# samd_board_des.net
KiCad netlist of a schematic drawn in EAGLE
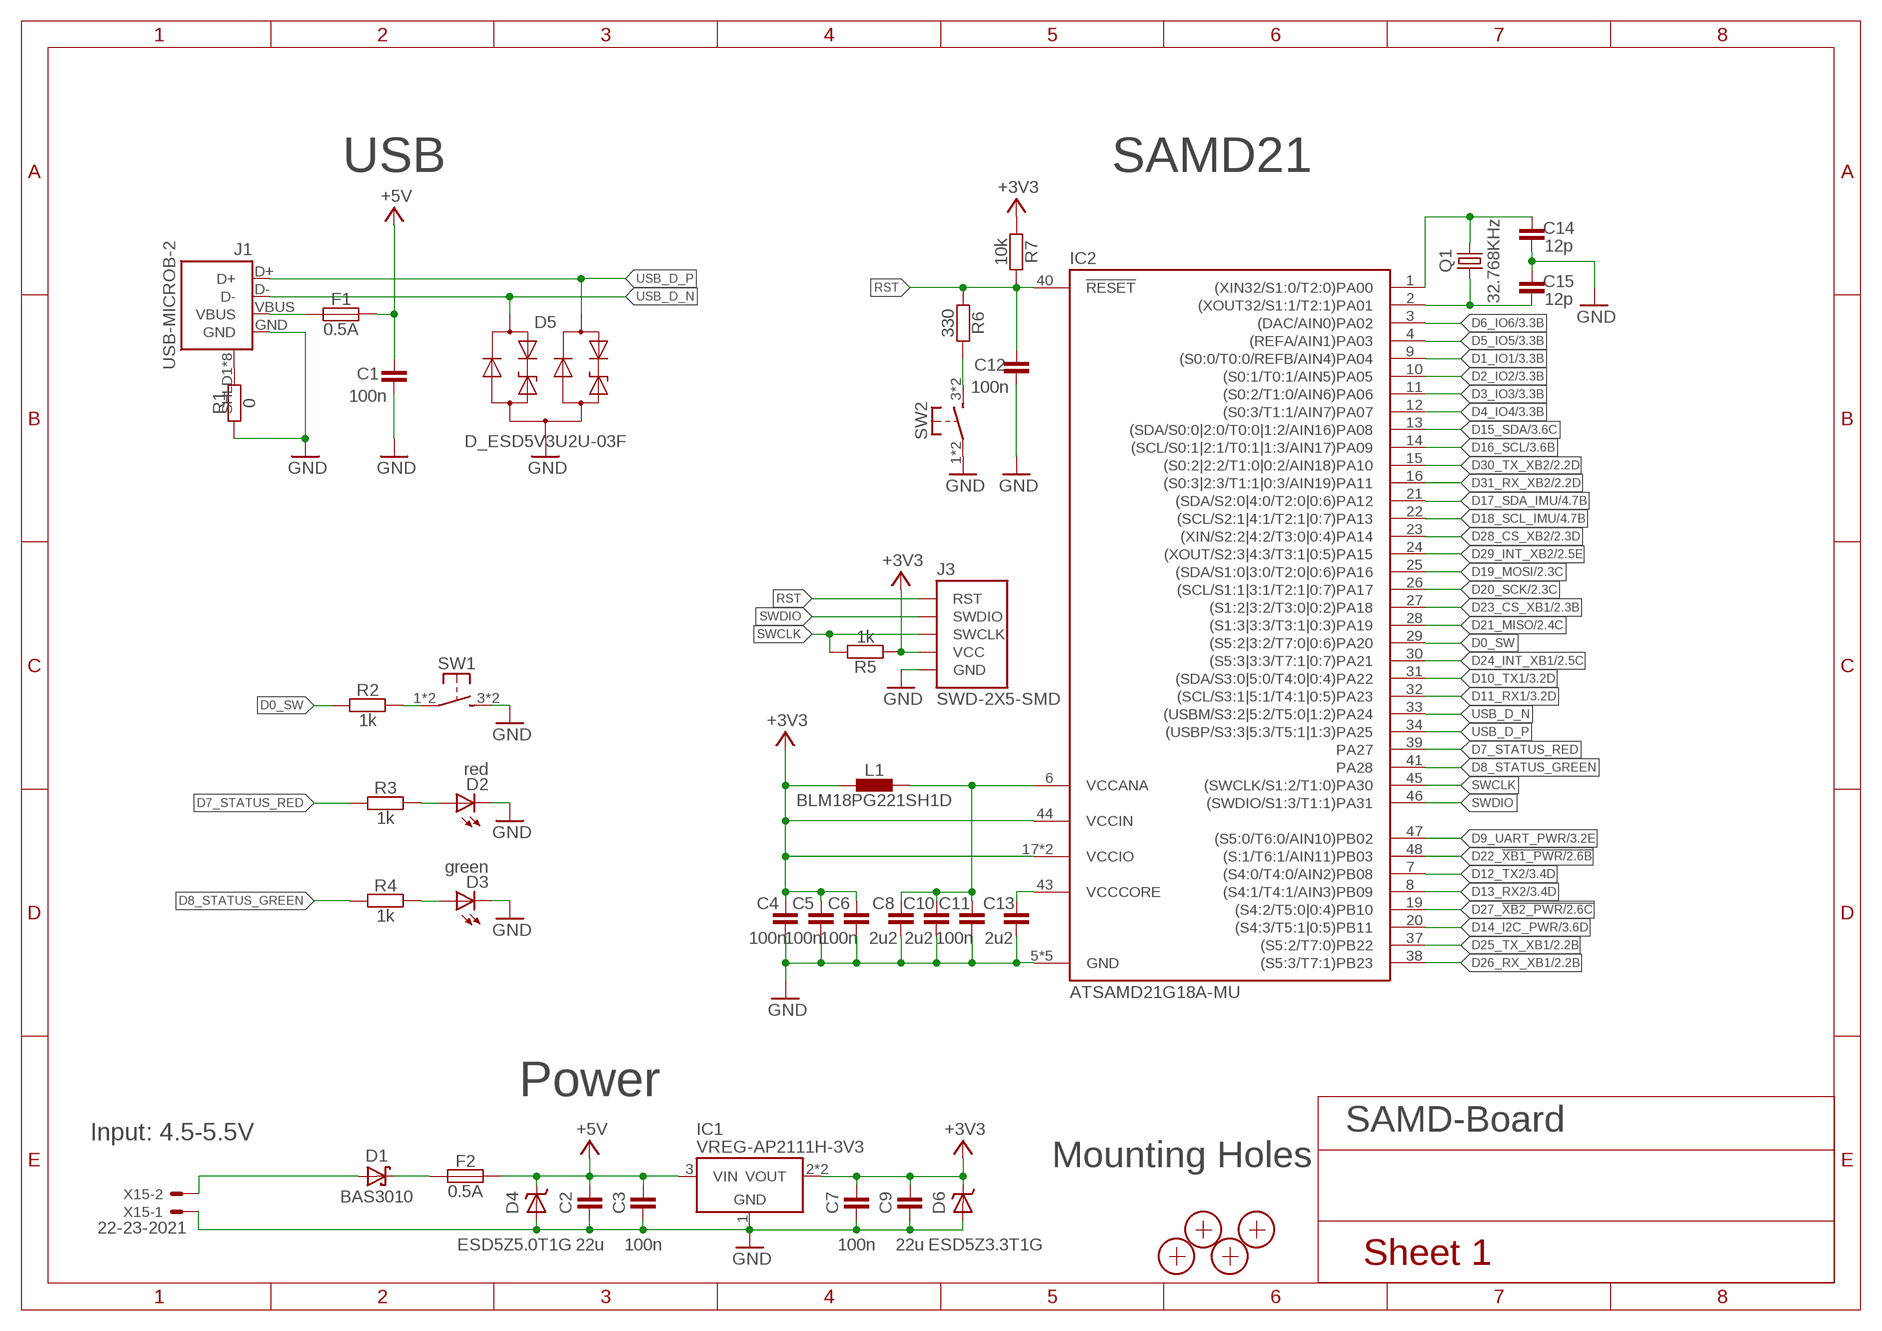
[diagram p0: schematic, sheet 1]
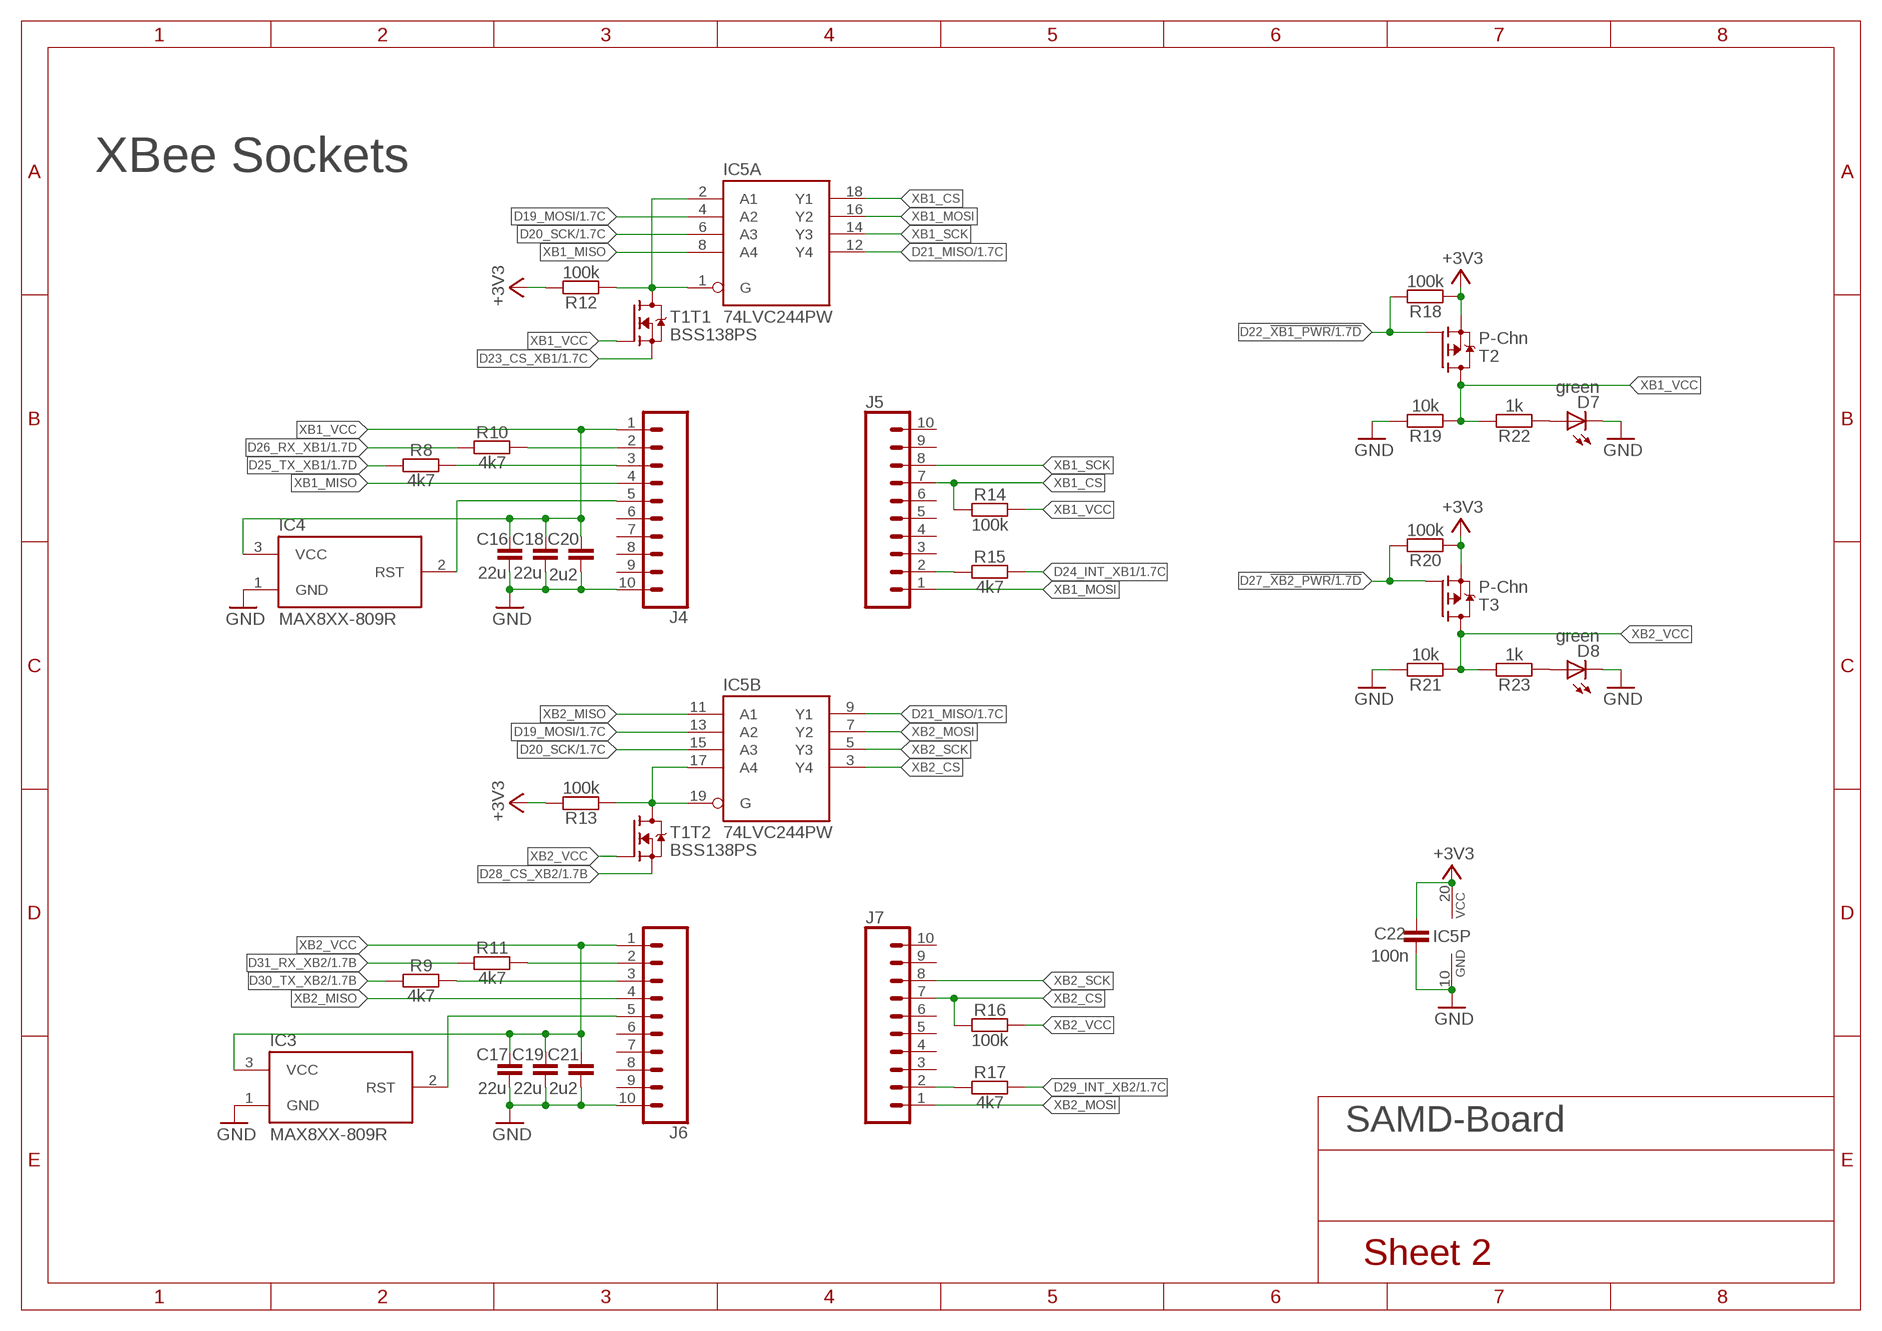
[diagram p1: schematic, sheet 2]
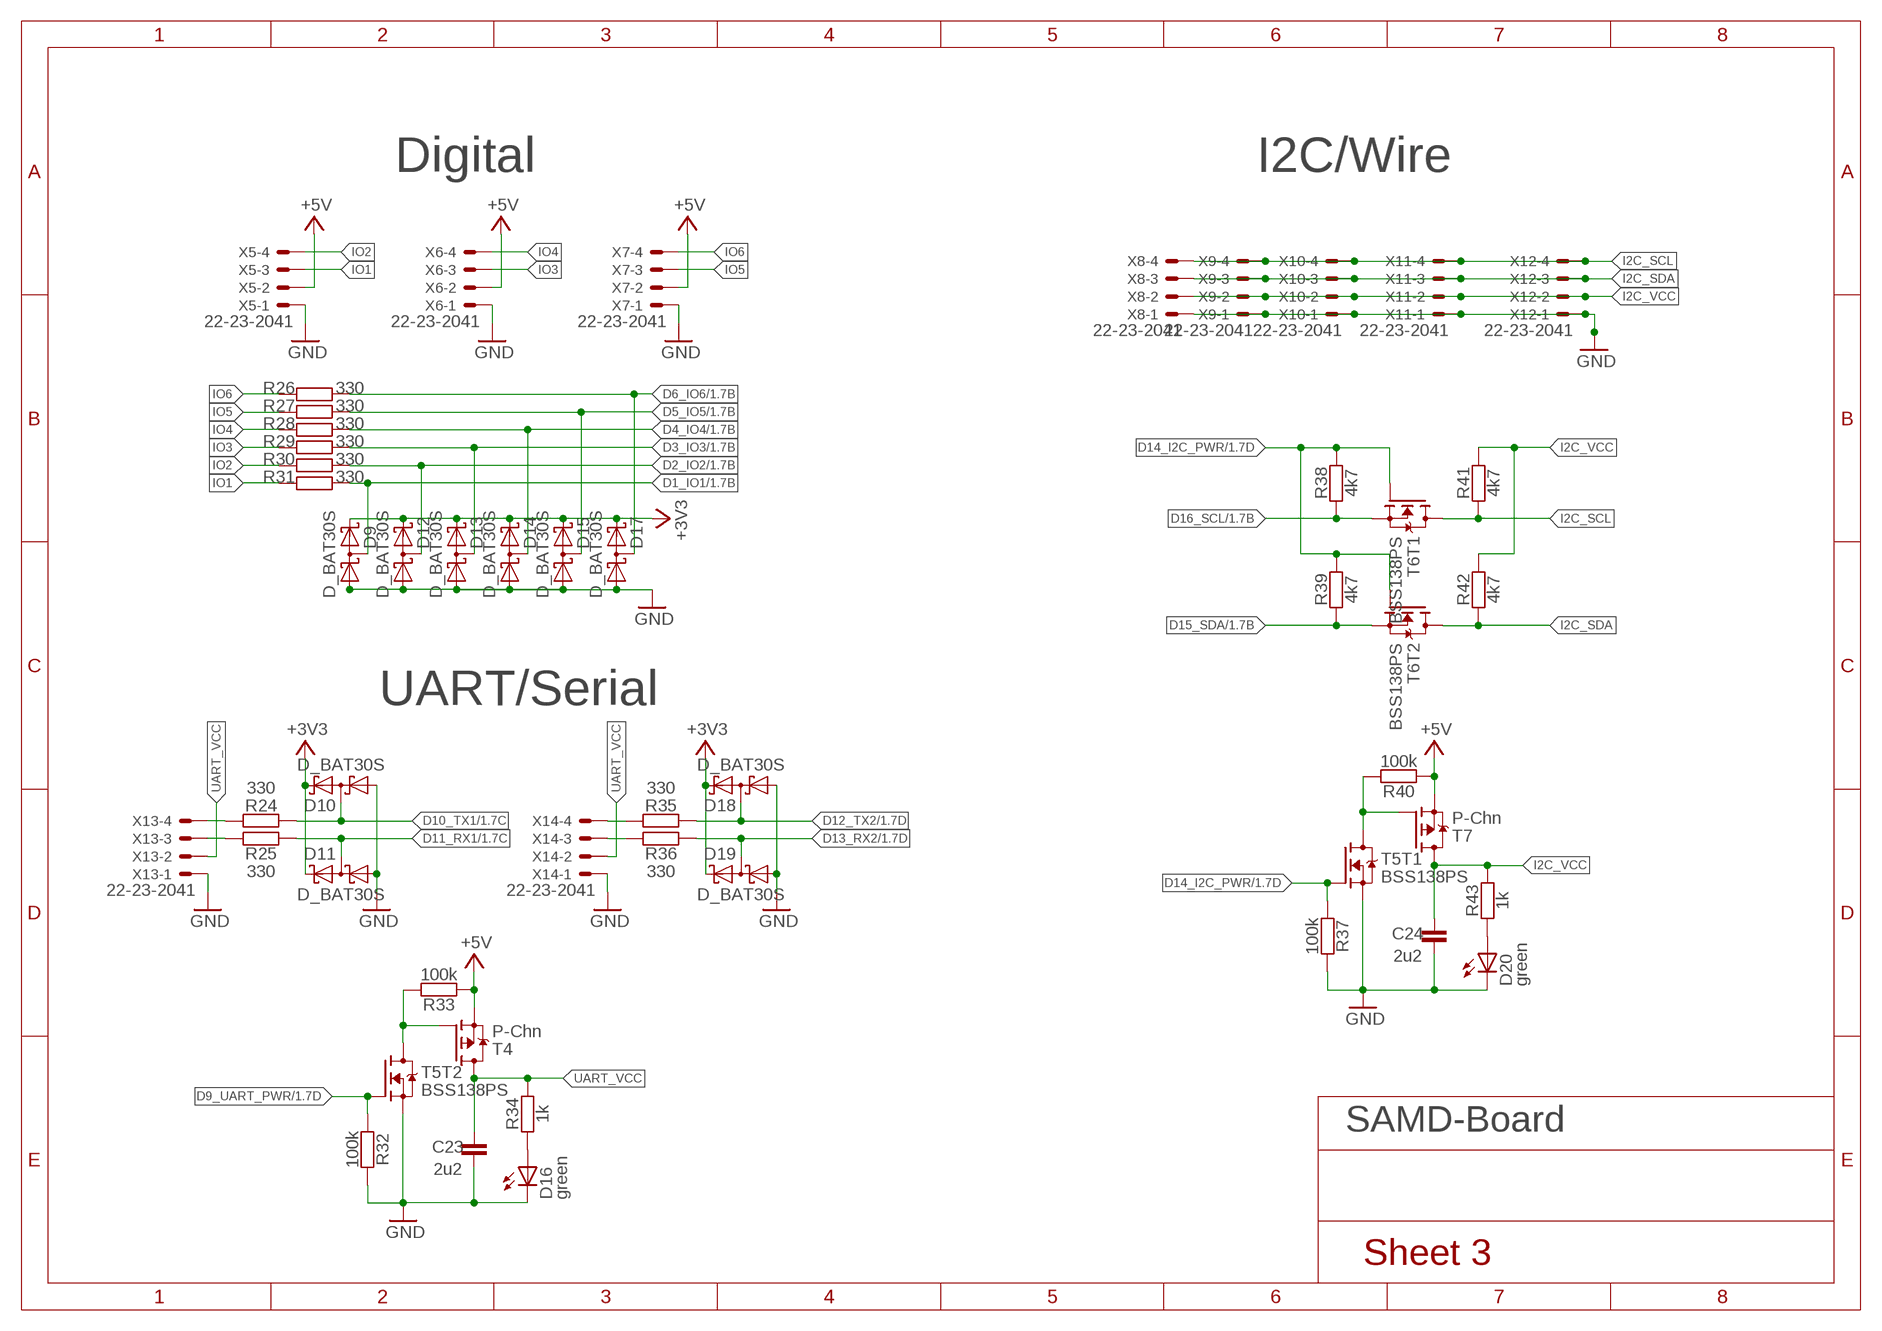
[diagram p2: schematic, sheet 3]
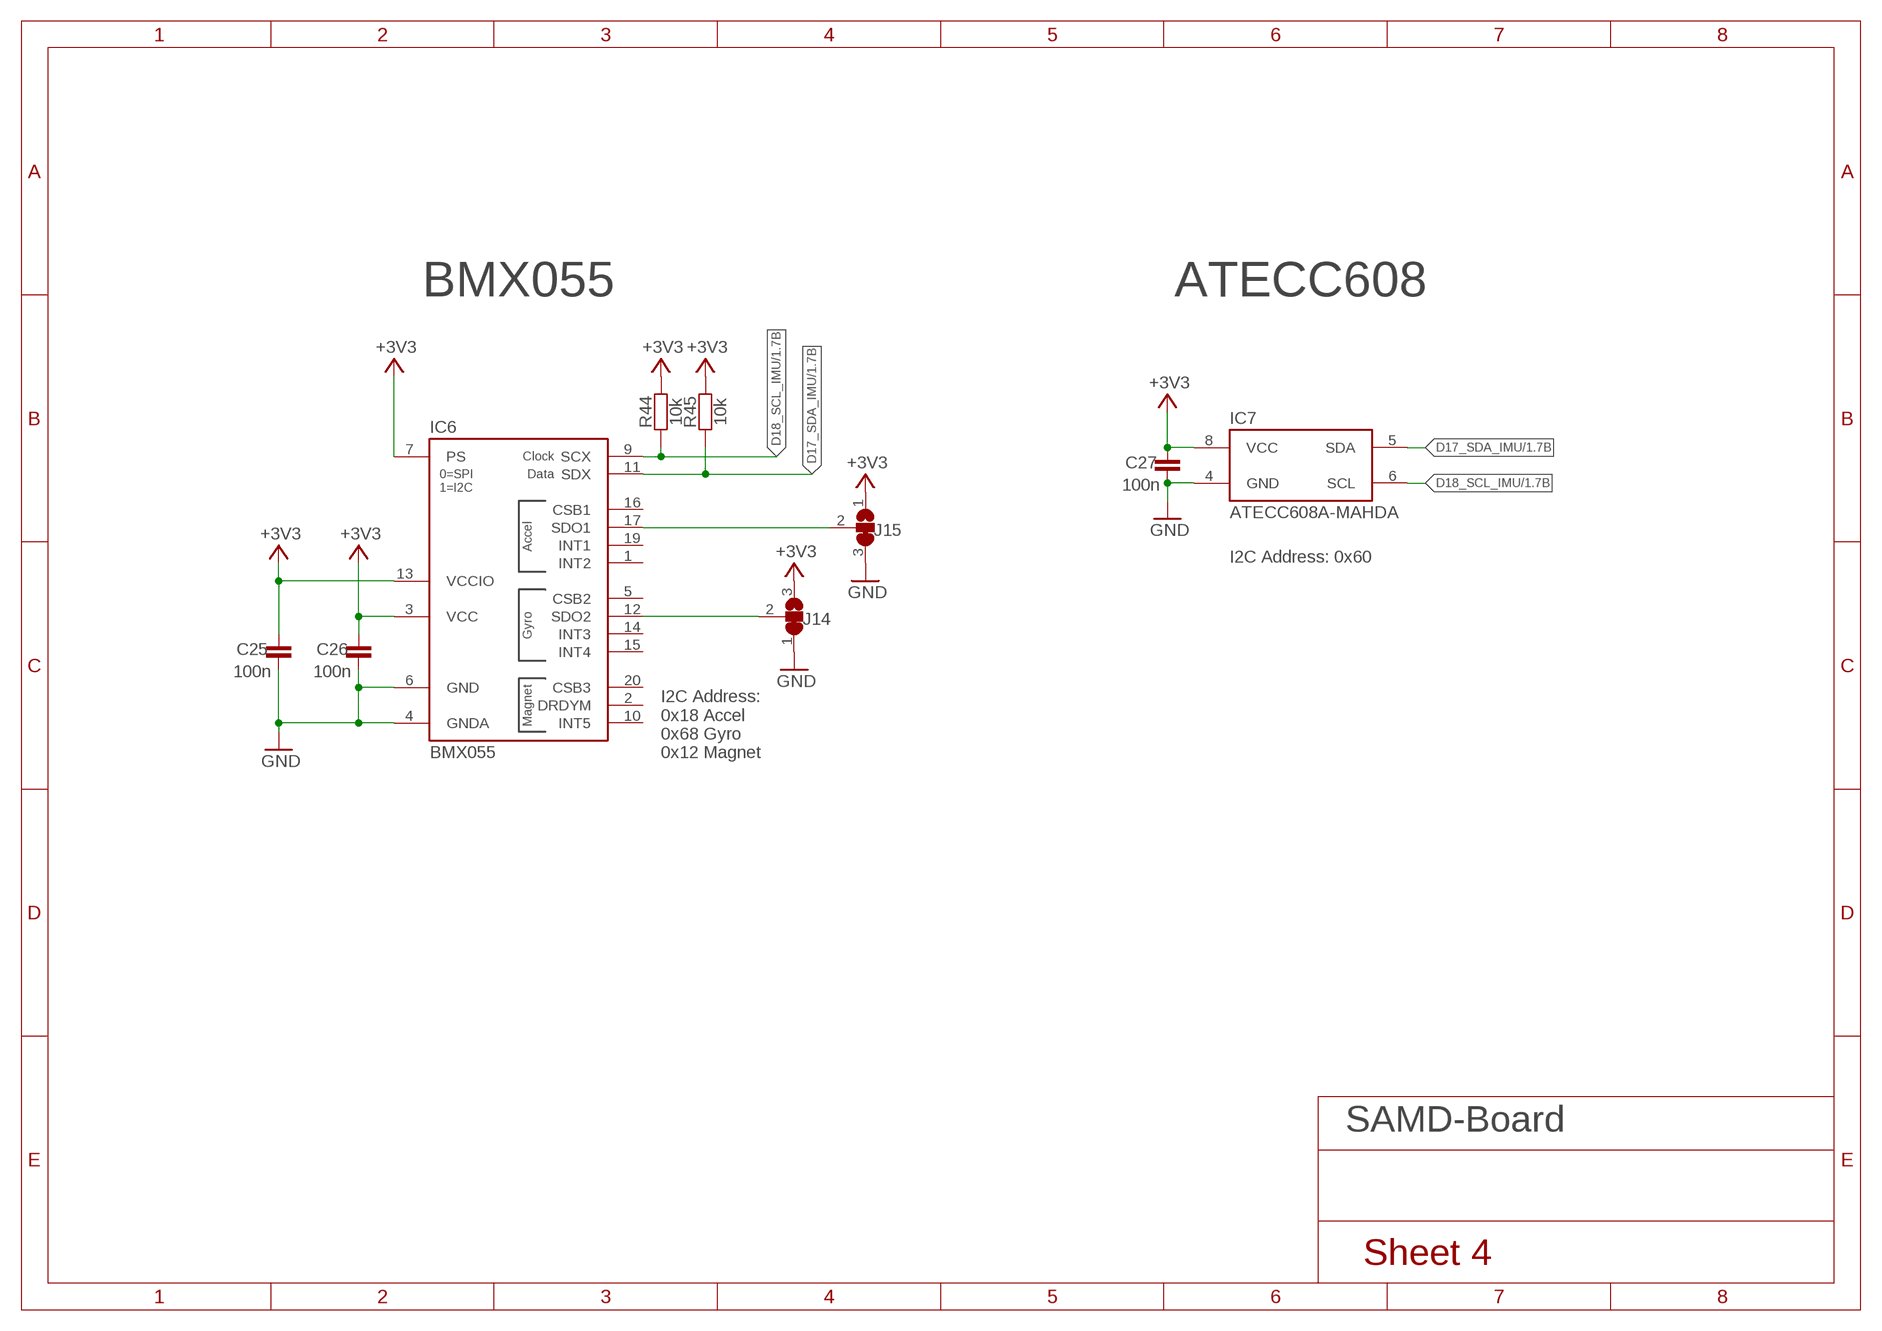
[diagram p3: schematic, sheet 4]

(export (version "E")
  (design (tool "Eeschema 10.0.6"))
  (components
    (comp (ref "C23")
      (value "2u2")
      (footprint "eagle-import:C0402")
      (libsource (lib "eagle-import") (part "CAPACITOR-0402"))
    )
    (comp (ref "C24")
      (value "2u2")
      (footprint "eagle-import:C0402")
      (libsource (lib "eagle-import") (part "CAPACITOR-0402"))
    )
    (comp (ref "D9")
      (value "D_BAT30S")
      (footprint "eagle-import:SOT323")
      (libsource (lib "eagle-import") (part "D_BAT30S"))
    )
    (comp (ref "D10")
      (value "D_BAT30S")
      (footprint "eagle-import:SOT323")
      (libsource (lib "eagle-import") (part "D_BAT30S"))
    )
    (comp (ref "D11")
      (value "D_BAT30S")
      (footprint "eagle-import:SOT323")
      (libsource (lib "eagle-import") (part "D_BAT30S"))
    )
    (comp (ref "D12")
      (value "D_BAT30S")
      (footprint "eagle-import:SOT323")
      (libsource (lib "eagle-import") (part "D_BAT30S"))
    )
    (comp (ref "D13")
      (value "D_BAT30S")
      (footprint "eagle-import:SOT323")
      (libsource (lib "eagle-import") (part "D_BAT30S"))
    )
    (comp (ref "D14")
      (value "D_BAT30S")
      (footprint "eagle-import:SOT323")
      (libsource (lib "eagle-import") (part "D_BAT30S"))
    )
    (comp (ref "D15")
      (value "D_BAT30S")
      (footprint "eagle-import:SOT323")
      (libsource (lib "eagle-import") (part "D_BAT30S"))
    )
    (comp (ref "D16")
      (value "green")
      (footprint "eagle-import:C0603")
      (libsource (lib "eagle-import") (part "LED-0603"))
    )
    (comp (ref "D17")
      (value "D_BAT30S")
      (footprint "eagle-import:SOT323")
      (libsource (lib "eagle-import") (part "D_BAT30S"))
    )
    (comp (ref "D18")
      (value "D_BAT30S")
      (footprint "eagle-import:SOT323")
      (libsource (lib "eagle-import") (part "D_BAT30S"))
    )
    (comp (ref "D19")
      (value "D_BAT30S")
      (footprint "eagle-import:SOT323")
      (libsource (lib "eagle-import") (part "D_BAT30S"))
    )
    (comp (ref "D20")
      (value "green")
      (footprint "eagle-import:C0603")
      (libsource (lib "eagle-import") (part "LED-0603"))
    )
    (comp (ref "R24")
      (value "330")
      (footprint "eagle-import:C0402")
      (libsource (lib "eagle-import") (part "RESISTOR-0402"))
    )
    (comp (ref "R25")
      (value "330")
      (footprint "eagle-import:C0402")
      (libsource (lib "eagle-import") (part "RESISTOR-0402"))
    )
    (comp (ref "R26")
      (value "330")
      (footprint "eagle-import:C0402")
      (libsource (lib "eagle-import") (part "RESISTOR-0402"))
    )
    (comp (ref "R27")
      (value "330")
      (footprint "eagle-import:C0402")
      (libsource (lib "eagle-import") (part "RESISTOR-0402"))
    )
    (comp (ref "R28")
      (value "330")
      (footprint "eagle-import:C0402")
      (libsource (lib "eagle-import") (part "RESISTOR-0402"))
    )
    (comp (ref "R29")
      (value "330")
      (footprint "eagle-import:C0402")
      (libsource (lib "eagle-import") (part "RESISTOR-0402"))
    )
    (comp (ref "R30")
      (value "330")
      (footprint "eagle-import:C0402")
      (libsource (lib "eagle-import") (part "RESISTOR-0402"))
    )
    (comp (ref "R31")
      (value "330")
      (footprint "eagle-import:C0402")
      (libsource (lib "eagle-import") (part "RESISTOR-0402"))
    )
    (comp (ref "R32")
      (value "100k")
      (footprint "eagle-import:C0402")
      (libsource (lib "eagle-import") (part "RESISTOR-0402"))
    )
    (comp (ref "R33")
      (value "100k")
      (footprint "eagle-import:C0402")
      (libsource (lib "eagle-import") (part "RESISTOR-0402"))
    )
    (comp (ref "R34")
      (value "1k")
      (footprint "eagle-import:C0402")
      (libsource (lib "eagle-import") (part "RESISTOR-0402"))
    )
    (comp (ref "R35")
      (value "330")
      (footprint "eagle-import:C0402")
      (libsource (lib "eagle-import") (part "RESISTOR-0402"))
    )
    (comp (ref "R36")
      (value "330")
      (footprint "eagle-import:C0402")
      (libsource (lib "eagle-import") (part "RESISTOR-0402"))
    )
    (comp (ref "R37")
      (value "100k")
      (footprint "eagle-import:C0402")
      (libsource (lib "eagle-import") (part "RESISTOR-0402"))
    )
    (comp (ref "R38")
      (value "4k7")
      (footprint "eagle-import:C0402")
      (libsource (lib "eagle-import") (part "RESISTOR-0402"))
    )
    (comp (ref "R39")
      (value "4k7")
      (footprint "eagle-import:C0402")
      (libsource (lib "eagle-import") (part "RESISTOR-0402"))
    )
    (comp (ref "R40")
      (value "100k")
      (footprint "eagle-import:C0402")
      (libsource (lib "eagle-import") (part "RESISTOR-0402"))
    )
    (comp (ref "R41")
      (value "4k7")
      (footprint "eagle-import:C0402")
      (libsource (lib "eagle-import") (part "RESISTOR-0402"))
    )
    (comp (ref "R42")
      (value "4k7")
      (footprint "eagle-import:C0402")
      (libsource (lib "eagle-import") (part "RESISTOR-0402"))
    )
    (comp (ref "R43")
      (value "1k")
      (footprint "eagle-import:C0402")
      (libsource (lib "eagle-import") (part "RESISTOR-0402"))
    )
    (comp (ref "T4")
      (value "P-Chn")
      (footprint "eagle-import:SOT23")
      (libsource (lib "eagle-import") (part "MOSFET-P-SOT23"))
    )
    (comp (ref "T5")
      (value "BSS138PS")
      (footprint "eagle-import:SOT363")
      (libsource (lib "eagle-import") (part "BSS138PS"))
    )
    (comp (ref "T6")
      (value "BSS138PS")
      (footprint "eagle-import:SOT363")
      (libsource (lib "eagle-import") (part "BSS138PS"))
    )
    (comp (ref "T7")
      (value "P-Chn")
      (footprint "eagle-import:SOT23")
      (libsource (lib "eagle-import") (part "MOSFET-P-SOT23"))
    )
    (comp (ref "X5")
      (value "22-23-2041")
      (footprint "eagle-import:22-23-2041")
      (fields (field (name "MF") "MOLEX"))
      (libsource (lib "eagle-import") (part "22-23-2041"))
    )
    (comp (ref "X6")
      (value "22-23-2041")
      (footprint "eagle-import:22-23-2041")
      (fields (field (name "MF") "MOLEX"))
      (libsource (lib "eagle-import") (part "22-23-2041"))
    )
    (comp (ref "X7")
      (value "22-23-2041")
      (footprint "eagle-import:22-23-2041")
      (fields (field (name "MF") "MOLEX"))
      (libsource (lib "eagle-import") (part "22-23-2041"))
    )
    (comp (ref "X8")
      (value "22-23-2041")
      (footprint "eagle-import:22-23-2041")
      (fields (field (name "MF") "MOLEX"))
      (libsource (lib "eagle-import") (part "22-23-2041"))
    )
    (comp (ref "X9")
      (value "22-23-2041")
      (footprint "eagle-import:22-23-2041")
      (fields (field (name "MF") "MOLEX"))
      (libsource (lib "eagle-import") (part "22-23-2041"))
    )
    (comp (ref "X10")
      (value "22-23-2041")
      (footprint "eagle-import:22-23-2041")
      (fields (field (name "MF") "MOLEX"))
      (libsource (lib "eagle-import") (part "22-23-2041"))
    )
    (comp (ref "X11")
      (value "22-23-2041")
      (footprint "eagle-import:22-23-2041")
      (fields (field (name "MF") "MOLEX"))
      (libsource (lib "eagle-import") (part "22-23-2041"))
    )
    (comp (ref "X12")
      (value "22-23-2041")
      (footprint "eagle-import:22-23-2041")
      (fields (field (name "MF") "MOLEX"))
      (libsource (lib "eagle-import") (part "22-23-2041"))
    )
    (comp (ref "X13")
      (value "22-23-2041")
      (footprint "eagle-import:22-23-2041")
      (fields (field (name "MF") "MOLEX"))
      (libsource (lib "eagle-import") (part "22-23-2041"))
    )
    (comp (ref "X14")
      (value "22-23-2041")
      (footprint "eagle-import:22-23-2041")
      (fields (field (name "MF") "MOLEX"))
      (libsource (lib "eagle-import") (part "22-23-2041"))
    )
    (comp (ref "C1")
      (value "100n")
      (footprint "eagle-import:C0402")
      (libsource (lib "eagle-import") (part "CAPACITOR-0402"))
    )
    (comp (ref "C2")
      (value "22u")
      (footprint "eagle-import:C0805")
      (libsource (lib "eagle-import") (part "CAPACITOR-0805"))
    )
    (comp (ref "C3")
      (value "100n")
      (footprint "eagle-import:C0402")
      (libsource (lib "eagle-import") (part "CAPACITOR-0402"))
    )
    (comp (ref "C4")
      (value "100n")
      (footprint "eagle-import:C0402")
      (libsource (lib "eagle-import") (part "CAPACITOR-0402"))
    )
    (comp (ref "C5")
      (value "100n")
      (footprint "eagle-import:C0402")
      (libsource (lib "eagle-import") (part "CAPACITOR-0402"))
    )
    (comp (ref "C6")
      (value "100n")
      (footprint "eagle-import:C0402")
      (libsource (lib "eagle-import") (part "CAPACITOR-0402"))
    )
    (comp (ref "C7")
      (value "100n")
      (footprint "eagle-import:C0402")
      (libsource (lib "eagle-import") (part "CAPACITOR-0402"))
    )
    (comp (ref "C8")
      (value "2u2")
      (footprint "eagle-import:C0402")
      (libsource (lib "eagle-import") (part "CAPACITOR-0402"))
    )
    (comp (ref "C9")
      (value "22u")
      (footprint "eagle-import:C0805")
      (libsource (lib "eagle-import") (part "CAPACITOR-0805"))
    )
    (comp (ref "C10")
      (value "2u2")
      (footprint "eagle-import:C0402")
      (libsource (lib "eagle-import") (part "CAPACITOR-0402"))
    )
    (comp (ref "C11")
      (value "100n")
      (footprint "eagle-import:C0402")
      (libsource (lib "eagle-import") (part "CAPACITOR-0402"))
    )
    (comp (ref "C12")
      (value "100n")
      (footprint "eagle-import:C0402")
      (libsource (lib "eagle-import") (part "CAPACITOR-0402"))
    )
    (comp (ref "C13")
      (value "2u2")
      (footprint "eagle-import:C0402")
      (libsource (lib "eagle-import") (part "CAPACITOR-0402"))
    )
    (comp (ref "C14")
      (value "12p")
      (footprint "eagle-import:C0402")
      (libsource (lib "eagle-import") (part "CAPACITOR-0402"))
    )
    (comp (ref "C15")
      (value "12p")
      (footprint "eagle-import:C0402")
      (libsource (lib "eagle-import") (part "CAPACITOR-0402"))
    )
    (comp (ref "D1")
      (value "BAS3010")
      (footprint "eagle-import:SOD323")
      (libsource (lib "eagle-import") (part "D_SCHOTTKY-SOD323"))
    )
    (comp (ref "D2")
      (value "red")
      (footprint "eagle-import:C0603")
      (libsource (lib "eagle-import") (part "LED-0603"))
    )
    (comp (ref "D3")
      (value "green")
      (footprint "eagle-import:C0603")
      (libsource (lib "eagle-import") (part "LED-0603"))
    )
    (comp (ref "D4")
      (value "ESD5Z5.0T1G")
      (footprint "eagle-import:SOD523")
      (libsource (lib "eagle-import") (part "D_TVS-SOD523"))
    )
    (comp (ref "D5")
      (value "D_ESD5V3U2U-03F")
      (footprint "eagle-import:SOT723")
      (libsource (lib "eagle-import") (part "D_ESD5V3U2U-03F"))
    )
    (comp (ref "D6")
      (value "ESD5Z3.3T1G")
      (footprint "eagle-import:SOD523")
      (libsource (lib "eagle-import") (part "D_TVS-SOD523"))
    )
    (comp (ref "F1")
      (value "0.5A")
      (footprint "eagle-import:C0805")
      (libsource (lib "eagle-import") (part "FUSE-0805"))
    )
    (comp (ref "F2")
      (value "0.5A")
      (footprint "eagle-import:C0805")
      (libsource (lib "eagle-import") (part "FUSE-0805"))
    )
    (comp (ref "IC1")
      (value "VREG-AP2111H-3V3")
      (footprint "eagle-import:SOT223")
      (libsource (lib "eagle-import") (part "VREG-TS1117CW-3V3"))
    )
    (comp (ref "IC2")
      (value "ATSAMD21G18A-MU")
      (footprint "eagle-import:QFN48-PAD")
      (libsource (lib "eagle-import") (part "ATSAMD21G18A-MU"))
    )
    (comp (ref "J1")
      (value "USB-MICROB-2")
      (footprint "eagle-import:USB-MICROB-10118194")
      (libsource (lib "eagle-import") (part "USB-MICROB-2"))
    )
    (comp (ref "J3")
      (value "SWD-2X5-SMD")
      (footprint "eagle-import:SWD-2X5_SMD")
      (libsource (lib "eagle-import") (part "SWD-2X5-SMD"))
    )
    (comp (ref "L1")
      (value "BLM18PG221SH1D")
      (footprint "eagle-import:C0603")
      (libsource (lib "eagle-import") (part "INDUCTOR-0603"))
    )
    (comp (ref "Q1")
      (value "32.768KHz")
      (footprint "eagle-import:CRYSTAL_ZM315")
      (libsource (lib "eagle-import") (part "CRYSTAL-ZM315"))
    )
    (comp (ref "R1")
      (value "0")
      (footprint "eagle-import:C0402")
      (libsource (lib "eagle-import") (part "RESISTOR-0402"))
    )
    (comp (ref "R2")
      (value "1k")
      (footprint "eagle-import:C0402")
      (libsource (lib "eagle-import") (part "RESISTOR-0402"))
    )
    (comp (ref "R3")
      (value "1k")
      (footprint "eagle-import:C0402")
      (libsource (lib "eagle-import") (part "RESISTOR-0402"))
    )
    (comp (ref "R4")
      (value "1k")
      (footprint "eagle-import:C0402")
      (libsource (lib "eagle-import") (part "RESISTOR-0402"))
    )
    (comp (ref "R5")
      (value "1k")
      (footprint "eagle-import:C0402")
      (libsource (lib "eagle-import") (part "RESISTOR-0402"))
    )
    (comp (ref "R6")
      (value "330")
      (footprint "eagle-import:C0402")
      (libsource (lib "eagle-import") (part "RESISTOR-0402"))
    )
    (comp (ref "R7")
      (value "10k")
      (footprint "eagle-import:C0402")
      (libsource (lib "eagle-import") (part "RESISTOR-0402"))
    )
    (comp (ref "SW1")
      (value "PTS645SH50SMTR92-Grey")
      (footprint "eagle-import:SW6X6_SMD")
      (libsource (lib "eagle-import") (part "SW-TACTILE-6X6_SMD"))
    )
    (comp (ref "SW2")
      (value "PTS645SK50SMTR92-Red")
      (footprint "eagle-import:SW6X6_SMD")
      (libsource (lib "eagle-import") (part "SW-TACTILE-6X6_SMD"))
    )
    (comp (ref "X1")
      (value "PASSER-07")
      (footprint "eagle-import:PASSER_07MM")
      (libsource (lib "eagle-import") (part "PASSER-07"))
    )
    (comp (ref "X2")
      (value "PASSER-07")
      (footprint "eagle-import:PASSER_07MM")
      (libsource (lib "eagle-import") (part "PASSER-07"))
    )
    (comp (ref "X3")
      (value "PASSER-07")
      (footprint "eagle-import:PASSER_07MM")
      (libsource (lib "eagle-import") (part "PASSER-07"))
    )
    (comp (ref "X4")
      (value "PASSER-07")
      (footprint "eagle-import:PASSER_07MM")
      (libsource (lib "eagle-import") (part "PASSER-07"))
    )
    (comp (ref "X15")
      (value "22-23-2021")
      (footprint "eagle-import:22-23-2021")
      (fields (field (name "MF") "MOLEX"))
      (libsource (lib "eagle-import") (part "22-23-2021"))
    )
    (comp (ref "C16")
      (value "22u")
      (footprint "eagle-import:C0805")
      (libsource (lib "eagle-import") (part "CAPACITOR-0805"))
    )
    (comp (ref "C17")
      (value "22u")
      (footprint "eagle-import:C0805")
      (libsource (lib "eagle-import") (part "CAPACITOR-0805"))
    )
    (comp (ref "C18")
      (value "22u")
      (footprint "eagle-import:C0805")
      (libsource (lib "eagle-import") (part "CAPACITOR-0805"))
    )
    (comp (ref "C19")
      (value "22u")
      (footprint "eagle-import:C0805")
      (libsource (lib "eagle-import") (part "CAPACITOR-0805"))
    )
    (comp (ref "C20")
      (value "2u2")
      (footprint "eagle-import:C0402")
      (libsource (lib "eagle-import") (part "CAPACITOR-0402"))
    )
    (comp (ref "C21")
      (value "2u2")
      (footprint "eagle-import:C0402")
      (libsource (lib "eagle-import") (part "CAPACITOR-0402"))
    )
    (comp (ref "C22")
      (value "100n")
      (footprint "eagle-import:C0402")
      (libsource (lib "eagle-import") (part "CAPACITOR-0402"))
    )
    (comp (ref "D7")
      (value "green")
      (footprint "eagle-import:C0603")
      (libsource (lib "eagle-import") (part "LED-0603"))
    )
    (comp (ref "D8")
      (value "green")
      (footprint "eagle-import:C0603")
      (libsource (lib "eagle-import") (part "LED-0603"))
    )
    (comp (ref "IC3")
      (value "MAX8XX-809R")
      (footprint "eagle-import:SOT23")
      (libsource (lib "eagle-import") (part "MAX8XX-809R"))
    )
    (comp (ref "IC4")
      (value "MAX8XX-809R")
      (footprint "eagle-import:SOT23")
      (libsource (lib "eagle-import") (part "MAX8XX-809R"))
    )
    (comp (ref "IC5")
      (value "74LVC244PW")
      (footprint "eagle-import:TSSOP20")
      (libsource (lib "eagle-import") (part "74244PWLVC"))
    )
    (comp (ref "J4")
      (value "CONN_102MM")
      (footprint "eagle-import:1X10-2MM")
      (libsource (lib "eagle-import") (part "CONN_102MM"))
    )
    (comp (ref "J5")
      (value "CONN_102MM")
      (footprint "eagle-import:1X10-2MM")
      (libsource (lib "eagle-import") (part "CONN_102MM"))
    )
    (comp (ref "J6")
      (value "CONN_102MM")
      (footprint "eagle-import:1X10-2MM")
      (libsource (lib "eagle-import") (part "CONN_102MM"))
    )
    (comp (ref "J7")
      (value "CONN_102MM")
      (footprint "eagle-import:1X10-2MM")
      (libsource (lib "eagle-import") (part "CONN_102MM"))
    )
    (comp (ref "R8")
      (value "4k7")
      (footprint "eagle-import:C0402")
      (libsource (lib "eagle-import") (part "RESISTOR-0402"))
    )
    (comp (ref "R9")
      (value "4k7")
      (footprint "eagle-import:C0402")
      (libsource (lib "eagle-import") (part "RESISTOR-0402"))
    )
    (comp (ref "R10")
      (value "4k7")
      (footprint "eagle-import:C0402")
      (libsource (lib "eagle-import") (part "RESISTOR-0402"))
    )
    (comp (ref "R11")
      (value "4k7")
      (footprint "eagle-import:C0402")
      (libsource (lib "eagle-import") (part "RESISTOR-0402"))
    )
    (comp (ref "R12")
      (value "100k")
      (footprint "eagle-import:C0402")
      (libsource (lib "eagle-import") (part "RESISTOR-0402"))
    )
    (comp (ref "R13")
      (value "100k")
      (footprint "eagle-import:C0402")
      (libsource (lib "eagle-import") (part "RESISTOR-0402"))
    )
    (comp (ref "R14")
      (value "100k")
      (footprint "eagle-import:C0402")
      (libsource (lib "eagle-import") (part "RESISTOR-0402"))
    )
    (comp (ref "R15")
      (value "4k7")
      (footprint "eagle-import:C0402")
      (libsource (lib "eagle-import") (part "RESISTOR-0402"))
    )
    (comp (ref "R16")
      (value "100k")
      (footprint "eagle-import:C0402")
      (libsource (lib "eagle-import") (part "RESISTOR-0402"))
    )
    (comp (ref "R17")
      (value "4k7")
      (footprint "eagle-import:C0402")
      (libsource (lib "eagle-import") (part "RESISTOR-0402"))
    )
    (comp (ref "R18")
      (value "100k")
      (footprint "eagle-import:C0402")
      (libsource (lib "eagle-import") (part "RESISTOR-0402"))
    )
    (comp (ref "R19")
      (value "10k")
      (footprint "eagle-import:C0402")
      (libsource (lib "eagle-import") (part "RESISTOR-0402"))
    )
    (comp (ref "R20")
      (value "100k")
      (footprint "eagle-import:C0402")
      (libsource (lib "eagle-import") (part "RESISTOR-0402"))
    )
    (comp (ref "R21")
      (value "10k")
      (footprint "eagle-import:C0402")
      (libsource (lib "eagle-import") (part "RESISTOR-0402"))
    )
    (comp (ref "R22")
      (value "1k")
      (footprint "eagle-import:C0402")
      (libsource (lib "eagle-import") (part "RESISTOR-0402"))
    )
    (comp (ref "R23")
      (value "1k")
      (footprint "eagle-import:C0402")
      (libsource (lib "eagle-import") (part "RESISTOR-0402"))
    )
    (comp (ref "T1")
      (value "BSS138PS")
      (footprint "eagle-import:SOT363")
      (libsource (lib "eagle-import") (part "BSS138PS"))
    )
    (comp (ref "T2")
      (value "P-Chn")
      (footprint "eagle-import:SOT23")
      (libsource (lib "eagle-import") (part "MOSFET-P-SOT23"))
    )
    (comp (ref "T3")
      (value "P-Chn")
      (footprint "eagle-import:SOT23")
      (libsource (lib "eagle-import") (part "MOSFET-P-SOT23"))
    )
    (comp (ref "C25")
      (value "100n")
      (footprint "eagle-import:C0402")
      (libsource (lib "eagle-import") (part "CAPACITOR-0402"))
    )
    (comp (ref "C26")
      (value "100n")
      (footprint "eagle-import:C0402")
      (libsource (lib "eagle-import") (part "CAPACITOR-0402"))
    )
    (comp (ref "C27")
      (value "100n")
      (footprint "eagle-import:C0402")
      (libsource (lib "eagle-import") (part "CAPACITOR-0402"))
    )
    (comp (ref "IC6")
      (value "BMX055")
      (footprint "eagle-import:BMX055")
      (libsource (lib "eagle-import") (part "BMX055"))
    )
    (comp (ref "IC7")
      (value "ATECC608A-MAHDA")
      (footprint "eagle-import:UDFN8")
      (libsource (lib "eagle-import") (part "ATECC608A-MAHDA"))
    )
    (comp (ref "J14")
      (value "JUMPER3-0402")
      (footprint "eagle-import:JUMPER3-0402")
      (libsource (lib "eagle-import") (part "JUMPER3-0402"))
    )
    (comp (ref "J15")
      (value "JUMPER3-0402")
      (footprint "eagle-import:JUMPER3-0402")
      (libsource (lib "eagle-import") (part "JUMPER3-0402"))
    )
    (comp (ref "R44")
      (value "10k")
      (footprint "eagle-import:C0402")
      (libsource (lib "eagle-import") (part "RESISTOR-0402"))
    )
    (comp (ref "R45")
      (value "10k")
      (footprint "eagle-import:C0402")
      (libsource (lib "eagle-import") (part "RESISTOR-0402"))
    )
  )
  (nets
    (net (code "1") (name "+3V3") (class "Default")
      (node (ref "C22") (pin "2") (pinfunction "2_2") (pintype "passive"))
      (node (ref "C25") (pin "2") (pinfunction "2_2") (pintype "passive"))
      (node (ref "C26") (pin "2") (pinfunction "2_2") (pintype "passive"))
      (node (ref "C27") (pin "2") (pinfunction "2_2") (pintype "passive"))
      (node (ref "C4") (pin "2") (pinfunction "2_2") (pintype "passive"))
      (node (ref "C5") (pin "2") (pinfunction "2_2") (pintype "passive"))
      (node (ref "C6") (pin "2") (pinfunction "2_2") (pintype "passive"))
      (node (ref "C7") (pin "2") (pinfunction "2_2") (pintype "passive"))
      (node (ref "C9") (pin "2") (pinfunction "2_2") (pintype "passive"))
      (node (ref "D10") (pin "2") (pinfunction "C_2") (pintype "passive"))
      (node (ref "D11") (pin "2") (pinfunction "C_2") (pintype "passive"))
      (node (ref "D12") (pin "2") (pinfunction "C_2") (pintype "passive"))
      (node (ref "D13") (pin "2") (pinfunction "C_2") (pintype "passive"))
      (node (ref "D14") (pin "2") (pinfunction "C_2") (pintype "passive"))
      (node (ref "D15") (pin "2") (pinfunction "C_2") (pintype "passive"))
      (node (ref "D17") (pin "2") (pinfunction "C_2") (pintype "passive"))
      (node (ref "D18") (pin "2") (pinfunction "C_2") (pintype "passive"))
      (node (ref "D19") (pin "2") (pinfunction "C_2") (pintype "passive"))
      (node (ref "D6") (pin "C") (pinfunction "C_C") (pintype "passive"))
      (node (ref "D9") (pin "2") (pinfunction "C_2") (pintype "passive"))
      (node (ref "IC1") (pin "2") (pinfunction "VOUT_2") (pintype "power_in"))
      (node (ref "IC1") (pin "4") (pinfunction "VOUT_4") (pintype "power_in"))
      (node (ref "IC2") (pin "17") (pinfunction "VCCIO_17") (pintype "power_in"))
      (node (ref "IC2") (pin "36") (pinfunction "VCCIO_36") (pintype "power_in"))
      (node (ref "IC2") (pin "44") (pinfunction "VCCIN_44") (pintype "power_in"))
      (node (ref "IC5") (pin "20") (pinfunction "VCC_20") (pintype "power_in"))
      (node (ref "IC6") (pin "13") (pinfunction "VCCIO_13") (pintype "power_in"))
      (node (ref "IC6") (pin "3") (pinfunction "VCC_3") (pintype "power_in"))
      (node (ref "IC6") (pin "7") (pinfunction "PS_7") (pintype "input"))
      (node (ref "IC7") (pin "8") (pinfunction "VCC_8") (pintype "power_in"))
      (node (ref "J14") (pin "3") (pinfunction "3_3") (pintype "passive"))
      (node (ref "J15") (pin "1") (pinfunction "1_1") (pintype "passive"))
      (node (ref "J3") (pin "VCC") (pinfunction "VCC_VCC") (pintype "power_in"))
      (node (ref "L1") (pin "1") (pinfunction "1_1") (pintype "passive"))
      (node (ref "R12") (pin "2") (pinfunction "2_2") (pintype "passive"))
      (node (ref "R13") (pin "2") (pinfunction "2_2") (pintype "passive"))
      (node (ref "R18") (pin "1") (pinfunction "1_1") (pintype "passive"))
      (node (ref "R20") (pin "1") (pinfunction "1_1") (pintype "passive"))
      (node (ref "R44") (pin "2") (pinfunction "2_2") (pintype "passive"))
      (node (ref "R45") (pin "2") (pinfunction "2_2") (pintype "passive"))
      (node (ref "R5") (pin "1") (pinfunction "1_1") (pintype "passive"))
      (node (ref "R7") (pin "1") (pinfunction "1_1") (pintype "passive"))
      (node (ref "T2") (pin "2") (pinfunction "S_2") (pintype "passive"))
      (node (ref "T3") (pin "2") (pinfunction "S_2") (pintype "passive"))
    )
    (net (code "2") (name "+5V") (class "Default")
      (node (ref "C1") (pin "2") (pinfunction "2_2") (pintype "passive"))
      (node (ref "C2") (pin "2") (pinfunction "2_2") (pintype "passive"))
      (node (ref "C3") (pin "2") (pinfunction "2_2") (pintype "passive"))
      (node (ref "D4") (pin "C") (pinfunction "C_C") (pintype "passive"))
      (node (ref "F1") (pin "2") (pinfunction "2_2") (pintype "passive"))
      (node (ref "F2") (pin "2") (pinfunction "2_2") (pintype "passive"))
      (node (ref "IC1") (pin "3") (pinfunction "VIN_3") (pintype "power_in"))
      (node (ref "R33") (pin "1") (pinfunction "1_1") (pintype "passive"))
      (node (ref "R40") (pin "1") (pinfunction "1_1") (pintype "passive"))
      (node (ref "T4") (pin "2") (pinfunction "S_2") (pintype "passive"))
      (node (ref "T7") (pin "2") (pinfunction "S_2") (pintype "passive"))
      (node (ref "X5") (pin "2") (pinfunction "S_2") (pintype "passive"))
      (node (ref "X6") (pin "2") (pinfunction "S_2") (pintype "passive"))
      (node (ref "X7") (pin "2") (pinfunction "S_2") (pintype "passive"))
    )
    (net (code "3") (name "D0_SW") (class "Default")
      (node (ref "IC2") (pin "29") (pinfunction "(S5:2|3:2/T7:0|0:6)PA20_29") (pintype "bidirectional"))
      (node (ref "R2") (pin "1") (pinfunction "1_1") (pintype "passive"))
    )
    (net (code "4") (name "D1_IO1") (class "Default")
      (node (ref "D9") (pin "3") (pinfunction "CA_3") (pintype "passive"))
      (node (ref "IC2") (pin "9") (pinfunction "(S0:0/T0:0/REFB/AIN4)PA04_9") (pintype "bidirectional"))
      (node (ref "R31") (pin "1") (pinfunction "1_1") (pintype "passive"))
    )
    (net (code "5") (name "D2_IO2") (class "Default")
      (node (ref "D12") (pin "3") (pinfunction "CA_3") (pintype "passive"))
      (node (ref "IC2") (pin "10") (pinfunction "(S0:1/T0:1/AIN5)PA05_10") (pintype "bidirectional"))
      (node (ref "R30") (pin "1") (pinfunction "1_1") (pintype "passive"))
    )
    (net (code "6") (name "D3_IO3") (class "Default")
      (node (ref "D13") (pin "3") (pinfunction "CA_3") (pintype "passive"))
      (node (ref "IC2") (pin "11") (pinfunction "(S0:2/T1:0/AIN6)PA06_11") (pintype "bidirectional"))
      (node (ref "R29") (pin "1") (pinfunction "1_1") (pintype "passive"))
    )
    (net (code "7") (name "D4_IO4") (class "Default")
      (node (ref "D14") (pin "3") (pinfunction "CA_3") (pintype "passive"))
      (node (ref "IC2") (pin "12") (pinfunction "(S0:3/T1:1/AIN7)PA07_12") (pintype "bidirectional"))
      (node (ref "R28") (pin "1") (pinfunction "1_1") (pintype "passive"))
    )
    (net (code "8") (name "D5_IO5") (class "Default")
      (node (ref "D15") (pin "3") (pinfunction "CA_3") (pintype "passive"))
      (node (ref "IC2") (pin "4") (pinfunction "(REFA/AIN1)PA03_4") (pintype "bidirectional"))
      (node (ref "R27") (pin "1") (pinfunction "1_1") (pintype "passive"))
    )
    (net (code "9") (name "D6_IO6") (class "Default")
      (node (ref "D17") (pin "3") (pinfunction "CA_3") (pintype "passive"))
      (node (ref "IC2") (pin "3") (pinfunction "(DAC/AIN0)PA02_3") (pintype "bidirectional"))
      (node (ref "R26") (pin "1") (pinfunction "1_1") (pintype "passive"))
    )
    (net (code "10") (name "D7_STATUS_RED") (class "Default")
      (node (ref "IC2") (pin "39") (pinfunction "PA27_39") (pintype "bidirectional"))
      (node (ref "R3") (pin "1") (pinfunction "1_1") (pintype "passive"))
    )
    (net (code "11") (name "D8_STATUS_GREEN") (class "Default")
      (node (ref "IC2") (pin "41") (pinfunction "PA28_41") (pintype "bidirectional"))
      (node (ref "R4") (pin "1") (pinfunction "1_1") (pintype "passive"))
    )
    (net (code "12") (name "D9_UART_PWR") (class "Default")
      (node (ref "IC2") (pin "47") (pinfunction "(S5:0/T6:0/AIN10)PB02_47") (pintype "bidirectional"))
      (node (ref "R32") (pin "1") (pinfunction "1_1") (pintype "passive"))
      (node (ref "T5") (pin "5") (pinfunction "G_5") (pintype "passive"))
    )
    (net (code "13") (name "D10_TX1") (class "Default")
      (node (ref "D10") (pin "3") (pinfunction "CA_3") (pintype "passive"))
      (node (ref "IC2") (pin "31") (pinfunction "(SDA/S3:0|5:0/T4:0|0:4)PA22_31") (pintype "bidirectional"))
      (node (ref "R24") (pin "1") (pinfunction "1_1") (pintype "passive"))
    )
    (net (code "14") (name "D11_RX1") (class "Default")
      (node (ref "D11") (pin "3") (pinfunction "CA_3") (pintype "passive"))
      (node (ref "IC2") (pin "32") (pinfunction "(SCL/S3:1|5:1/T4:1|0:5)PA23_32") (pintype "bidirectional"))
      (node (ref "R25") (pin "1") (pinfunction "1_1") (pintype "passive"))
    )
    (net (code "15") (name "D12_TX2") (class "Default")
      (node (ref "D18") (pin "3") (pinfunction "CA_3") (pintype "passive"))
      (node (ref "IC2") (pin "7") (pinfunction "(S4:0/T4:0/AIN2)PB08_7") (pintype "bidirectional"))
      (node (ref "R35") (pin "1") (pinfunction "1_1") (pintype "passive"))
    )
    (net (code "16") (name "D13_RX2") (class "Default")
      (node (ref "D19") (pin "3") (pinfunction "CA_3") (pintype "passive"))
      (node (ref "IC2") (pin "8") (pinfunction "(S4:1/T4:1/AIN3)PB09_8") (pintype "bidirectional"))
      (node (ref "R36") (pin "1") (pinfunction "1_1") (pintype "passive"))
    )
    (net (code "17") (name "D14_I2C_PWR") (class "Default")
      (node (ref "IC2") (pin "20") (pinfunction "(S4:3/T5:1|0:5)PB11_20") (pintype "bidirectional"))
      (node (ref "R37") (pin "1") (pinfunction "1_1") (pintype "passive"))
      (node (ref "R38") (pin "2") (pinfunction "2_2") (pintype "passive"))
      (node (ref "R39") (pin "2") (pinfunction "2_2") (pintype "passive"))
      (node (ref "T5") (pin "2") (pinfunction "G_2") (pintype "passive"))
      (node (ref "T6") (pin "2") (pinfunction "G_2") (pintype "passive"))
      (node (ref "T6") (pin "5") (pinfunction "G_5") (pintype "passive"))
    )
    (net (code "18") (name "D15_SDA") (class "Default")
      (node (ref "IC2") (pin "13") (pinfunction "(SDA/S0:0|2:0/T0:0|1:2/AIN16)PA08_13") (pintype "bidirectional"))
      (node (ref "R39") (pin "1") (pinfunction "1_1") (pintype "passive"))
      (node (ref "T6") (pin "4") (pinfunction "S_4") (pintype "passive"))
    )
    (net (code "19") (name "D16_SCL") (class "Default")
      (node (ref "IC2") (pin "14") (pinfunction "(SCL/S0:1|2:1/T0:1|1:3/AIN17)PA09_14") (pintype "bidirectional"))
      (node (ref "R38") (pin "1") (pinfunction "1_1") (pintype "passive"))
      (node (ref "T6") (pin "1") (pinfunction "S_1") (pintype "passive"))
    )
    (net (code "20") (name "D17_SDA_IMU") (class "Default")
      (node (ref "IC2") (pin "21") (pinfunction "(SDA/S2:0|4:0/T2:0|0:6)PA12_21") (pintype "bidirectional"))
      (node (ref "IC6") (pin "11") (pinfunction "SDX_11") (pintype "bidirectional"))
      (node (ref "IC7") (pin "5") (pinfunction "SDA_5") (pintype "bidirectional"))
      (node (ref "R45") (pin "1") (pinfunction "1_1") (pintype "passive"))
    )
    (net (code "21") (name "D18_SCL_IMU") (class "Default")
      (node (ref "IC2") (pin "22") (pinfunction "(SCL/S2:1|4:1/T2:1|0:7)PA13_22") (pintype "bidirectional"))
      (node (ref "IC6") (pin "9") (pinfunction "SCX_9") (pintype "bidirectional"))
      (node (ref "IC7") (pin "6") (pinfunction "SCL_6") (pintype "bidirectional"))
      (node (ref "R44") (pin "1") (pinfunction "1_1") (pintype "passive"))
    )
    (net (code "22") (name "D19_MOSI") (class "Default")
      (node (ref "IC2") (pin "25") (pinfunction "(SDA/S1:0|3:0/T2:0|0:6)PA16_25") (pintype "bidirectional"))
      (node (ref "IC5") (pin "13") (pinfunction "A2_13") (pintype "input"))
      (node (ref "IC5") (pin "4") (pinfunction "A2_4") (pintype "input"))
    )
    (net (code "23") (name "D20_SCK") (class "Default")
      (node (ref "IC2") (pin "26") (pinfunction "(SCL/S1:1|3:1/T2:1|0:7)PA17_26") (pintype "bidirectional"))
      (node (ref "IC5") (pin "15") (pinfunction "A3_15") (pintype "input"))
      (node (ref "IC5") (pin "6") (pinfunction "A3_6") (pintype "input"))
    )
    (net (code "24") (name "D21_MISO") (class "Default")
      (node (ref "IC2") (pin "28") (pinfunction "(S1:3|3:3/T3:1|0:3)PA19_28") (pintype "bidirectional"))
      (node (ref "IC5") (pin "12") (pinfunction "Y4_12") (pintype "tri_state"))
      (node (ref "IC5") (pin "9") (pinfunction "Y1_9") (pintype "tri_state"))
    )
    (net (code "25") (name "D22_~{XB1_PWR}") (class "Default")
      (node (ref "IC2") (pin "48") (pinfunction "(S:1/T6:1/AIN11)PB03_48") (pintype "bidirectional"))
      (node (ref "R18") (pin "2") (pinfunction "2_2") (pintype "passive"))
      (node (ref "T2") (pin "1") (pinfunction "G_1") (pintype "passive"))
    )
    (net (code "26") (name "D23_CS_XB1") (class "Default")
      (node (ref "IC2") (pin "27") (pinfunction "(S1:2|3:2/T3:0|0:2)PA18_27") (pintype "bidirectional"))
      (node (ref "T1") (pin "1") (pinfunction "S_1") (pintype "passive"))
    )
    (net (code "27") (name "D24_INT_XB1") (class "Default")
      (node (ref "IC2") (pin "30") (pinfunction "(S5:3|3:3/T7:1|0:7)PA21_30") (pintype "bidirectional"))
      (node (ref "R15") (pin "2") (pinfunction "2_2") (pintype "passive"))
    )
    (net (code "28") (name "D25_TX_XB1") (class "Default")
      (node (ref "IC2") (pin "37") (pinfunction "(S5:2/T7:0)PB22_37") (pintype "bidirectional"))
      (node (ref "R8") (pin "1") (pinfunction "1_1") (pintype "passive"))
    )
    (net (code "29") (name "D26_RX_XB1") (class "Default")
      (node (ref "IC2") (pin "38") (pinfunction "(S5:3/T7:1)PB23_38") (pintype "bidirectional"))
      (node (ref "R10") (pin "1") (pinfunction "1_1") (pintype "passive"))
    )
    (net (code "30") (name "D27_~{XB2_PWR}") (class "Default")
      (node (ref "IC2") (pin "19") (pinfunction "(S4:2/T5:0|0:4)PB10_19") (pintype "bidirectional"))
      (node (ref "R20") (pin "2") (pinfunction "2_2") (pintype "passive"))
      (node (ref "T3") (pin "1") (pinfunction "G_1") (pintype "passive"))
    )
    (net (code "31") (name "D28_CS_XB2") (class "Default")
      (node (ref "IC2") (pin "23") (pinfunction "(XIN/S2:2|4:2/T3:0|0:4)PA14_23") (pintype "bidirectional"))
      (node (ref "T1") (pin "4") (pinfunction "S_4") (pintype "passive"))
    )
    (net (code "32") (name "D29_INT_XB2") (class "Default")
      (node (ref "IC2") (pin "24") (pinfunction "(XOUT/S2:3|4:3/T3:1|0:5)PA15_24") (pintype "bidirectional"))
      (node (ref "R17") (pin "2") (pinfunction "2_2") (pintype "passive"))
    )
    (net (code "33") (name "D30_TX_XB2") (class "Default")
      (node (ref "IC2") (pin "15") (pinfunction "(S0:2|2:2/T1:0|0:2/AIN18)PA10_15") (pintype "bidirectional"))
      (node (ref "R9") (pin "1") (pinfunction "1_1") (pintype "passive"))
    )
    (net (code "34") (name "D31_RX_XB2") (class "Default")
      (node (ref "IC2") (pin "16") (pinfunction "(S0:3|2:3/T1:1|0:3/AIN19)PA11_16") (pintype "bidirectional"))
      (node (ref "R11") (pin "1") (pinfunction "1_1") (pintype "passive"))
    )
    (net (code "35") (name "GND") (class "Default")
      (node (ref "C1") (pin "1") (pinfunction "1_1") (pintype "passive"))
      (node (ref "C10") (pin "1") (pinfunction "1_1") (pintype "passive"))
      (node (ref "C11") (pin "1") (pinfunction "1_1") (pintype "passive"))
      (node (ref "C12") (pin "1") (pinfunction "1_1") (pintype "passive"))
      (node (ref "C13") (pin "1") (pinfunction "1_1") (pintype "passive"))
      (node (ref "C14") (pin "2") (pinfunction "2_2") (pintype "passive"))
      (node (ref "C15") (pin "1") (pinfunction "1_1") (pintype "passive"))
      (node (ref "C16") (pin "1") (pinfunction "1_1") (pintype "passive"))
      (node (ref "C17") (pin "1") (pinfunction "1_1") (pintype "passive"))
      (node (ref "C18") (pin "1") (pinfunction "1_1") (pintype "passive"))
      (node (ref "C19") (pin "1") (pinfunction "1_1") (pintype "passive"))
      (node (ref "C2") (pin "1") (pinfunction "1_1") (pintype "passive"))
      (node (ref "C20") (pin "1") (pinfunction "1_1") (pintype "passive"))
      (node (ref "C21") (pin "1") (pinfunction "1_1") (pintype "passive"))
      (node (ref "C22") (pin "1") (pinfunction "1_1") (pintype "passive"))
      (node (ref "C23") (pin "1") (pinfunction "1_1") (pintype "passive"))
      (node (ref "C24") (pin "1") (pinfunction "1_1") (pintype "passive"))
      (node (ref "C25") (pin "1") (pinfunction "1_1") (pintype "passive"))
      (node (ref "C26") (pin "1") (pinfunction "1_1") (pintype "passive"))
      (node (ref "C27") (pin "1") (pinfunction "1_1") (pintype "passive"))
      (node (ref "C3") (pin "1") (pinfunction "1_1") (pintype "passive"))
      (node (ref "C4") (pin "1") (pinfunction "1_1") (pintype "passive"))
      (node (ref "C5") (pin "1") (pinfunction "1_1") (pintype "passive"))
      (node (ref "C6") (pin "1") (pinfunction "1_1") (pintype "passive"))
      (node (ref "C7") (pin "1") (pinfunction "1_1") (pintype "passive"))
      (node (ref "C8") (pin "1") (pinfunction "1_1") (pintype "passive"))
      (node (ref "C9") (pin "1") (pinfunction "1_1") (pintype "passive"))
      (node (ref "D10") (pin "1") (pinfunction "A_1") (pintype "passive"))
      (node (ref "D11") (pin "1") (pinfunction "A_1") (pintype "passive"))
      (node (ref "D12") (pin "1") (pinfunction "A_1") (pintype "passive"))
      (node (ref "D13") (pin "1") (pinfunction "A_1") (pintype "passive"))
      (node (ref "D14") (pin "1") (pinfunction "A_1") (pintype "passive"))
      (node (ref "D15") (pin "1") (pinfunction "A_1") (pintype "passive"))
      (node (ref "D16") (pin "C") (pinfunction "C_C") (pintype "passive"))
      (node (ref "D17") (pin "1") (pinfunction "A_1") (pintype "passive"))
      (node (ref "D18") (pin "1") (pinfunction "A_1") (pintype "passive"))
      (node (ref "D19") (pin "1") (pinfunction "A_1") (pintype "passive"))
      (node (ref "D2") (pin "C") (pinfunction "C_C") (pintype "passive"))
      (node (ref "D20") (pin "C") (pinfunction "C_C") (pintype "passive"))
      (node (ref "D3") (pin "C") (pinfunction "C_C") (pintype "passive"))
      (node (ref "D4") (pin "A") (pinfunction "A_A") (pintype "passive"))
      (node (ref "D5") (pin "3") (pinfunction "A_3") (pintype "passive"))
      (node (ref "D6") (pin "A") (pinfunction "A_A") (pintype "passive"))
      (node (ref "D7") (pin "C") (pinfunction "C_C") (pintype "passive"))
      (node (ref "D8") (pin "C") (pinfunction "C_C") (pintype "passive"))
      (node (ref "D9") (pin "1") (pinfunction "A_1") (pintype "passive"))
      (node (ref "IC1") (pin "1") (pinfunction "GND_1") (pintype "power_in"))
      (node (ref "IC2") (pin "18") (pinfunction "GND_18") (pintype "power_in"))
      (node (ref "IC2") (pin "35") (pinfunction "GND_35") (pintype "power_in"))
      (node (ref "IC2") (pin "42") (pinfunction "GND_42") (pintype "power_in"))
      (node (ref "IC2") (pin "5") (pinfunction "GND_5") (pintype "power_in"))
      (node (ref "IC2") (pin "TP") (pinfunction "GND_TP") (pintype "power_in"))
      (node (ref "IC3") (pin "1") (pinfunction "GND_1") (pintype "power_in"))
      (node (ref "IC4") (pin "1") (pinfunction "GND_1") (pintype "power_in"))
      (node (ref "IC5") (pin "10") (pinfunction "GND_10") (pintype "power_in"))
      (node (ref "IC6") (pin "4") (pinfunction "GNDA_4") (pintype "power_in"))
      (node (ref "IC6") (pin "6") (pinfunction "GND_6") (pintype "power_in"))
      (node (ref "IC7") (pin "4") (pinfunction "GND_4") (pintype "power_in"))
      (node (ref "J1") (pin "GND") (pinfunction "GND_GND") (pintype "power_in"))
      (node (ref "J14") (pin "1") (pinfunction "1_1") (pintype "passive"))
      (node (ref "J15") (pin "3") (pinfunction "3_3") (pintype "passive"))
      (node (ref "J3") (pin "GND@1") (pinfunction "GND_GND@1") (pintype "power_in"))
      (node (ref "J3") (pin "GND@2") (pinfunction "GND_GND@2") (pintype "power_in"))
      (node (ref "J3") (pin "GND@3") (pinfunction "GND_GND@3") (pintype "power_in"))
      (node (ref "J4") (pin "10") (pinfunction "10_10") (pintype "passive"))
      (node (ref "J6") (pin "10") (pinfunction "10_10") (pintype "passive"))
      (node (ref "R1") (pin "1") (pinfunction "1_1") (pintype "passive"))
      (node (ref "R19") (pin "2") (pinfunction "2_2") (pintype "passive"))
      (node (ref "R21") (pin "2") (pinfunction "2_2") (pintype "passive"))
      (node (ref "R32") (pin "2") (pinfunction "2_2") (pintype "passive"))
      (node (ref "R37") (pin "2") (pinfunction "2_2") (pintype "passive"))
      (node (ref "SW1") (pin "3") (pinfunction "S1_3") (pintype "passive"))
      (node (ref "SW1") (pin "4") (pinfunction "S1_4") (pintype "passive"))
      (node (ref "SW2") (pin "1") (pinfunction "P1_1") (pintype "passive"))
      (node (ref "SW2") (pin "2") (pinfunction "P1_2") (pintype "passive"))
      (node (ref "T5") (pin "1") (pinfunction "S_1") (pintype "passive"))
      (node (ref "T5") (pin "4") (pinfunction "S_4") (pintype "passive"))
      (node (ref "X10") (pin "1") (pinfunction "S_1") (pintype "passive"))
      (node (ref "X11") (pin "1") (pinfunction "S_1") (pintype "passive"))
      (node (ref "X12") (pin "1") (pinfunction "S_1") (pintype "passive"))
      (node (ref "X13") (pin "1") (pinfunction "S_1") (pintype "passive"))
      (node (ref "X14") (pin "1") (pinfunction "S_1") (pintype "passive"))
      (node (ref "X15") (pin "1") (pinfunction "S_1") (pintype "passive"))
      (node (ref "X5") (pin "1") (pinfunction "S_1") (pintype "passive"))
      (node (ref "X6") (pin "1") (pinfunction "S_1") (pintype "passive"))
      (node (ref "X7") (pin "1") (pinfunction "S_1") (pintype "passive"))
      (node (ref "X8") (pin "1") (pinfunction "S_1") (pintype "passive"))
      (node (ref "X9") (pin "1") (pinfunction "S_1") (pintype "passive"))
    )
    (net (code "36") (name "I2C_SCL") (class "Default")
      (node (ref "R41") (pin "1") (pinfunction "1_1") (pintype "passive"))
      (node (ref "T6") (pin "6") (pinfunction "D_6") (pintype "passive"))
      (node (ref "X10") (pin "4") (pinfunction "S_4") (pintype "passive"))
      (node (ref "X11") (pin "4") (pinfunction "S_4") (pintype "passive"))
      (node (ref "X12") (pin "4") (pinfunction "S_4") (pintype "passive"))
      (node (ref "X8") (pin "4") (pinfunction "S_4") (pintype "passive"))
      (node (ref "X9") (pin "4") (pinfunction "S_4") (pintype "passive"))
    )
    (net (code "37") (name "I2C_SDA") (class "Default")
      (node (ref "R42") (pin "1") (pinfunction "1_1") (pintype "passive"))
      (node (ref "T6") (pin "3") (pinfunction "D_3") (pintype "passive"))
      (node (ref "X10") (pin "3") (pinfunction "S_3") (pintype "passive"))
      (node (ref "X11") (pin "3") (pinfunction "S_3") (pintype "passive"))
      (node (ref "X12") (pin "3") (pinfunction "S_3") (pintype "passive"))
      (node (ref "X8") (pin "3") (pinfunction "S_3") (pintype "passive"))
      (node (ref "X9") (pin "3") (pinfunction "S_3") (pintype "passive"))
    )
    (net (code "38") (name "I2C_VCC") (class "Default")
      (node (ref "C24") (pin "2") (pinfunction "2_2") (pintype "passive"))
      (node (ref "R41") (pin "2") (pinfunction "2_2") (pintype "passive"))
      (node (ref "R42") (pin "2") (pinfunction "2_2") (pintype "passive"))
      (node (ref "R43") (pin "2") (pinfunction "2_2") (pintype "passive"))
      (node (ref "T7") (pin "3") (pinfunction "D_3") (pintype "passive"))
      (node (ref "X10") (pin "2") (pinfunction "S_2") (pintype "passive"))
      (node (ref "X11") (pin "2") (pinfunction "S_2") (pintype "passive"))
      (node (ref "X12") (pin "2") (pinfunction "S_2") (pintype "passive"))
      (node (ref "X8") (pin "2") (pinfunction "S_2") (pintype "passive"))
      (node (ref "X9") (pin "2") (pinfunction "S_2") (pintype "passive"))
    )
    (net (code "39") (name "IO1") (class "Default")
      (node (ref "R31") (pin "2") (pinfunction "2_2") (pintype "passive"))
      (node (ref "X5") (pin "3") (pinfunction "S_3") (pintype "passive"))
    )
    (net (code "40") (name "IO2") (class "Default")
      (node (ref "R30") (pin "2") (pinfunction "2_2") (pintype "passive"))
      (node (ref "X5") (pin "4") (pinfunction "S_4") (pintype "passive"))
    )
    (net (code "41") (name "IO3") (class "Default")
      (node (ref "R29") (pin "2") (pinfunction "2_2") (pintype "passive"))
      (node (ref "X6") (pin "3") (pinfunction "S_3") (pintype "passive"))
    )
    (net (code "42") (name "IO4") (class "Default")
      (node (ref "R28") (pin "2") (pinfunction "2_2") (pintype "passive"))
      (node (ref "X6") (pin "4") (pinfunction "S_4") (pintype "passive"))
    )
    (net (code "43") (name "IO5") (class "Default")
      (node (ref "R27") (pin "2") (pinfunction "2_2") (pintype "passive"))
      (node (ref "X7") (pin "3") (pinfunction "S_3") (pintype "passive"))
    )
    (net (code "44") (name "IO6") (class "Default")
      (node (ref "R26") (pin "2") (pinfunction "2_2") (pintype "passive"))
      (node (ref "X7") (pin "4") (pinfunction "S_4") (pintype "passive"))
    )
    (net (code "45") (name "Net-(D1-PadC)") (class "Default")
      (node (ref "D1") (pin "C") (pinfunction "C_C") (pintype "passive"))
      (node (ref "F2") (pin "1") (pinfunction "1_1") (pintype "passive"))
    )
    (net (code "46") (name "Net-(D2-PadA)") (class "Default")
      (node (ref "D2") (pin "A") (pinfunction "A_A") (pintype "passive"))
      (node (ref "R3") (pin "2") (pinfunction "2_2") (pintype "passive"))
    )
    (net (code "47") (name "Net-(D3-PadA)") (class "Default")
      (node (ref "D3") (pin "A") (pinfunction "A_A") (pintype "passive"))
      (node (ref "R4") (pin "2") (pinfunction "2_2") (pintype "passive"))
    )
    (net (code "48") (name "Net-(D7-PadA)") (class "Default")
      (node (ref "D7") (pin "A") (pinfunction "A_A") (pintype "passive"))
      (node (ref "R22") (pin "1") (pinfunction "1_1") (pintype "passive"))
    )
    (net (code "49") (name "Net-(D8-PadA)") (class "Default")
      (node (ref "D8") (pin "A") (pinfunction "A_A") (pintype "passive"))
      (node (ref "R23") (pin "1") (pinfunction "1_1") (pintype "passive"))
    )
    (net (code "50") (name "Net-(D16-PadA)") (class "Default")
      (node (ref "D16") (pin "A") (pinfunction "A_A") (pintype "passive"))
      (node (ref "R34") (pin "1") (pinfunction "1_1") (pintype "passive"))
    )
    (net (code "51") (name "Net-(D20-PadA)") (class "Default")
      (node (ref "D20") (pin "A") (pinfunction "A_A") (pintype "passive"))
      (node (ref "R43") (pin "1") (pinfunction "1_1") (pintype "passive"))
    )
    (net (code "52") (name "Net-(F1-Pad1)") (class "Default")
      (node (ref "F1") (pin "1") (pinfunction "1_1") (pintype "passive"))
      (node (ref "J1") (pin "VBUS") (pinfunction "VBUS_VBUS") (pintype "power_in"))
    )
    (net (code "53") (name "Net-(IC2-(XIN32{slash}S1:0{slash}T2:0)PA00)") (class "Default")
      (node (ref "C14") (pin "1") (pinfunction "1_1") (pintype "passive"))
      (node (ref "IC2") (pin "1") (pinfunction "(XIN32/S1:0/T2:0)PA00_1") (pintype "bidirectional"))
      (node (ref "Q1") (pin "2") (pinfunction "2_2") (pintype "passive"))
    )
    (net (code "54") (name "Net-(IC2-(XOUT32{slash}S1:1{slash}T2:1)PA01)") (class "Default")
      (node (ref "C15") (pin "2") (pinfunction "2_2") (pintype "passive"))
      (node (ref "IC2") (pin "2") (pinfunction "(XOUT32/S1:1/T2:1)PA01_2") (pintype "bidirectional"))
      (node (ref "Q1") (pin "1") (pinfunction "1_1") (pintype "passive"))
    )
    (net (code "55") (name "Net-(IC2-VCCANA)") (class "Default")
      (node (ref "C10") (pin "2") (pinfunction "2_2") (pintype "passive"))
      (node (ref "C11") (pin "2") (pinfunction "2_2") (pintype "passive"))
      (node (ref "C8") (pin "2") (pinfunction "2_2") (pintype "passive"))
      (node (ref "IC2") (pin "6") (pinfunction "VCCANA_6") (pintype "power_in"))
      (node (ref "L1") (pin "2") (pinfunction "2_2") (pintype "passive"))
    )
    (net (code "56") (name "Net-(IC2-VCCCORE)") (class "Default")
      (node (ref "C13") (pin "2") (pinfunction "2_2") (pintype "passive"))
      (node (ref "IC2") (pin "43") (pinfunction "VCCCORE_43") (pintype "power_in"))
    )
    (net (code "57") (name "Net-(IC3-RST)") (class "Default")
      (node (ref "IC3") (pin "2") (pinfunction "RST_2") (pintype "output"))
      (node (ref "J6") (pin "5") (pinfunction "5_5") (pintype "passive"))
    )
    (net (code "58") (name "Net-(IC4-RST)") (class "Default")
      (node (ref "IC4") (pin "2") (pinfunction "RST_2") (pintype "output"))
      (node (ref "J4") (pin "5") (pinfunction "5_5") (pintype "passive"))
    )
    (net (code "59") (name "Net-(IC5A-A1)") (class "Default")
      (node (ref "IC5") (pin "1") (pinfunction "G_1") (pintype "input"))
      (node (ref "IC5") (pin "2") (pinfunction "A1_2") (pintype "input"))
      (node (ref "R12") (pin "1") (pinfunction "1_1") (pintype "passive"))
      (node (ref "T1") (pin "6") (pinfunction "D_6") (pintype "passive"))
    )
    (net (code "60") (name "Net-(IC5B-A4)") (class "Default")
      (node (ref "IC5") (pin "17") (pinfunction "A4_17") (pintype "input"))
      (node (ref "IC5") (pin "19") (pinfunction "G_19") (pintype "input"))
      (node (ref "R13") (pin "1") (pinfunction "1_1") (pintype "passive"))
      (node (ref "T1") (pin "3") (pinfunction "D_3") (pintype "passive"))
    )
    (net (code "61") (name "Net-(IC6-SDO1)") (class "Default")
      (node (ref "IC6") (pin "17") (pinfunction "SDO1_17") (pintype "bidirectional"))
      (node (ref "J15") (pin "2") (pinfunction "2_2") (pintype "passive"))
    )
    (net (code "62") (name "Net-(IC6-SDO2)") (class "Default")
      (node (ref "IC6") (pin "12") (pinfunction "SDO2_12") (pintype "bidirectional"))
      (node (ref "J14") (pin "2") (pinfunction "2_2") (pintype "passive"))
    )
    (net (code "63") (name "Net-(J1-SHIELD-PadSHLD1)") (class "Default")
      (node (ref "J1") (pin "SHLD1") (pinfunction "SHIELD_SHLD1") (pintype "passive"))
      (node (ref "J1") (pin "SHLD2") (pinfunction "SHIELD_SHLD2") (pintype "passive"))
      (node (ref "J1") (pin "SHLD3") (pinfunction "SHIELD_SHLD3") (pintype "passive"))
      (node (ref "J1") (pin "SHLD4") (pinfunction "SHIELD_SHLD4") (pintype "passive"))
      (node (ref "J1") (pin "SHLD5") (pinfunction "SHIELD_SHLD5") (pintype "passive"))
      (node (ref "J1") (pin "SHLD6") (pinfunction "SHIELD_SHLD6") (pintype "passive"))
      (node (ref "J1") (pin "SHLD7") (pinfunction "SHIELD_SHLD7") (pintype "passive"))
      (node (ref "J1") (pin "SHLD8") (pinfunction "SHIELD_SHLD8") (pintype "passive"))
      (node (ref "R1") (pin "2") (pinfunction "2_2") (pintype "passive"))
    )
    (net (code "64") (name "Net-(J4-Pad2)") (class "Default")
      (node (ref "J4") (pin "2") (pinfunction "2_2") (pintype "passive"))
      (node (ref "R10") (pin "2") (pinfunction "2_2") (pintype "passive"))
    )
    (net (code "65") (name "Net-(J4-Pad3)") (class "Default")
      (node (ref "J4") (pin "3") (pinfunction "3_3") (pintype "passive"))
      (node (ref "R8") (pin "2") (pinfunction "2_2") (pintype "passive"))
    )
    (net (code "66") (name "Net-(J5-Pad2)") (class "Default")
      (node (ref "J5") (pin "2") (pinfunction "2_2") (pintype "passive"))
      (node (ref "R15") (pin "1") (pinfunction "1_1") (pintype "passive"))
    )
    (net (code "67") (name "Net-(J6-Pad2)") (class "Default")
      (node (ref "J6") (pin "2") (pinfunction "2_2") (pintype "passive"))
      (node (ref "R11") (pin "2") (pinfunction "2_2") (pintype "passive"))
    )
    (net (code "68") (name "Net-(J6-Pad3)") (class "Default")
      (node (ref "J6") (pin "3") (pinfunction "3_3") (pintype "passive"))
      (node (ref "R9") (pin "2") (pinfunction "2_2") (pintype "passive"))
    )
    (net (code "69") (name "Net-(J7-Pad2)") (class "Default")
      (node (ref "J7") (pin "2") (pinfunction "2_2") (pintype "passive"))
      (node (ref "R17") (pin "1") (pinfunction "1_1") (pintype "passive"))
    )
    (net (code "70") (name "Net-(R2-Pad2)") (class "Default")
      (node (ref "R2") (pin "2") (pinfunction "2_2") (pintype "passive"))
      (node (ref "SW1") (pin "1") (pinfunction "P1_1") (pintype "passive"))
      (node (ref "SW1") (pin "2") (pinfunction "P1_2") (pintype "passive"))
    )
    (net (code "71") (name "Net-(R6-Pad2)") (class "Default")
      (node (ref "R6") (pin "2") (pinfunction "2_2") (pintype "passive"))
      (node (ref "SW2") (pin "3") (pinfunction "S1_3") (pintype "passive"))
      (node (ref "SW2") (pin "4") (pinfunction "S1_4") (pintype "passive"))
    )
    (net (code "72") (name "Net-(T4-G)") (class "Default")
      (node (ref "R33") (pin "2") (pinfunction "2_2") (pintype "passive"))
      (node (ref "T4") (pin "1") (pinfunction "G_1") (pintype "passive"))
      (node (ref "T5") (pin "3") (pinfunction "D_3") (pintype "passive"))
    )
    (net (code "73") (name "Net-(T5A-D)") (class "Default")
      (node (ref "R40") (pin "2") (pinfunction "2_2") (pintype "passive"))
      (node (ref "T5") (pin "6") (pinfunction "D_6") (pintype "passive"))
      (node (ref "T7") (pin "1") (pinfunction "G_1") (pintype "passive"))
    )
    (net (code "74") (name "Net-(X13C-S)") (class "Default")
      (node (ref "R25") (pin "2") (pinfunction "2_2") (pintype "passive"))
      (node (ref "X13") (pin "3") (pinfunction "S_3") (pintype "passive"))
    )
    (net (code "75") (name "Net-(X13D-S)") (class "Default")
      (node (ref "R24") (pin "2") (pinfunction "2_2") (pintype "passive"))
      (node (ref "X13") (pin "4") (pinfunction "S_4") (pintype "passive"))
    )
    (net (code "76") (name "Net-(X14C-S)") (class "Default")
      (node (ref "R36") (pin "2") (pinfunction "2_2") (pintype "passive"))
      (node (ref "X14") (pin "3") (pinfunction "S_3") (pintype "passive"))
    )
    (net (code "77") (name "Net-(X14D-S)") (class "Default")
      (node (ref "R35") (pin "2") (pinfunction "2_2") (pintype "passive"))
      (node (ref "X14") (pin "4") (pinfunction "S_4") (pintype "passive"))
    )
    (net (code "78") (name "Net-(X15B-S)") (class "Default")
      (node (ref "D1") (pin "A") (pinfunction "A_A") (pintype "passive"))
      (node (ref "X15") (pin "2") (pinfunction "S_2") (pintype "passive"))
    )
    (net (code "79") (name "RST") (class "Default")
      (node (ref "C12") (pin "2") (pinfunction "2_2") (pintype "passive"))
      (node (ref "IC2") (pin "40") (pinfunction "~{RESET}_40") (pintype "input"))
      (node (ref "J3") (pin "RST") (pinfunction "RST_RST") (pintype "bidirectional"))
      (node (ref "R6") (pin "1") (pinfunction "1_1") (pintype "passive"))
      (node (ref "R7") (pin "2") (pinfunction "2_2") (pintype "passive"))
    )
    (net (code "80") (name "SWCLK") (class "Default")
      (node (ref "IC2") (pin "45") (pinfunction "(SWCLK/S1:2/T1:0)PA30_45") (pintype "bidirectional"))
      (node (ref "J3") (pin "SWCLK") (pinfunction "SWCLK_SWCLK") (pintype "bidirectional"))
      (node (ref "R5") (pin "2") (pinfunction "2_2") (pintype "passive"))
    )
    (net (code "81") (name "SWDIO") (class "Default")
      (node (ref "IC2") (pin "46") (pinfunction "(SWDIO/S1:3/T1:1)PA31_46") (pintype "bidirectional"))
      (node (ref "J3") (pin "SWDIO") (pinfunction "SWDIO_SWDIO") (pintype "bidirectional"))
    )
    (net (code "82") (name "UART_VCC") (class "Default")
      (node (ref "C23") (pin "2") (pinfunction "2_2") (pintype "passive"))
      (node (ref "R34") (pin "2") (pinfunction "2_2") (pintype "passive"))
      (node (ref "T4") (pin "3") (pinfunction "D_3") (pintype "passive"))
      (node (ref "X13") (pin "2") (pinfunction "S_2") (pintype "passive"))
      (node (ref "X14") (pin "2") (pinfunction "S_2") (pintype "passive"))
    )
    (net (code "83") (name "USB_D_N") (class "Default")
      (node (ref "D5") (pin "1") (pinfunction "C1_1") (pintype "passive"))
      (node (ref "IC2") (pin "33") (pinfunction "(USBM/S3:2|5:2/T5:0|1:2)PA24_33") (pintype "bidirectional"))
      (node (ref "J1") (pin "D-") (pinfunction "D-_D-") (pintype "bidirectional"))
    )
    (net (code "84") (name "USB_D_P") (class "Default")
      (node (ref "D5") (pin "2") (pinfunction "C2_2") (pintype "passive"))
      (node (ref "IC2") (pin "34") (pinfunction "(USBP/S3:3|5:3/T5:1|1:3)PA25_34") (pintype "bidirectional"))
      (node (ref "J1") (pin "D+") (pinfunction "D+_D+") (pintype "bidirectional"))
    )
    (net (code "85") (name "XB1_CS") (class "Default")
      (node (ref "IC5") (pin "18") (pinfunction "Y1_18") (pintype "tri_state"))
      (node (ref "J5") (pin "7") (pinfunction "7_7") (pintype "passive"))
      (node (ref "R14") (pin "1") (pinfunction "1_1") (pintype "passive"))
    )
    (net (code "86") (name "XB1_MISO") (class "Default")
      (node (ref "IC5") (pin "8") (pinfunction "A4_8") (pintype "input"))
      (node (ref "J4") (pin "4") (pinfunction "4_4") (pintype "passive"))
    )
    (net (code "87") (name "XB1_MOSI") (class "Default")
      (node (ref "IC5") (pin "16") (pinfunction "Y2_16") (pintype "tri_state"))
      (node (ref "J5") (pin "1") (pinfunction "1_1") (pintype "passive"))
    )
    (net (code "88") (name "XB1_SCK") (class "Default")
      (node (ref "IC5") (pin "14") (pinfunction "Y3_14") (pintype "tri_state"))
      (node (ref "J5") (pin "8") (pinfunction "8_8") (pintype "passive"))
    )
    (net (code "89") (name "XB1_VCC") (class "Default")
      (node (ref "C16") (pin "2") (pinfunction "2_2") (pintype "passive"))
      (node (ref "C18") (pin "2") (pinfunction "2_2") (pintype "passive"))
      (node (ref "C20") (pin "2") (pinfunction "2_2") (pintype "passive"))
      (node (ref "IC4") (pin "3") (pinfunction "VCC_3") (pintype "power_in"))
      (node (ref "J4") (pin "1") (pinfunction "1_1") (pintype "passive"))
      (node (ref "R14") (pin "2") (pinfunction "2_2") (pintype "passive"))
      (node (ref "R19") (pin "1") (pinfunction "1_1") (pintype "passive"))
      (node (ref "R22") (pin "2") (pinfunction "2_2") (pintype "passive"))
      (node (ref "T1") (pin "2") (pinfunction "G_2") (pintype "passive"))
      (node (ref "T2") (pin "3") (pinfunction "D_3") (pintype "passive"))
    )
    (net (code "90") (name "XB2_CS") (class "Default")
      (node (ref "IC5") (pin "3") (pinfunction "Y4_3") (pintype "tri_state"))
      (node (ref "J7") (pin "7") (pinfunction "7_7") (pintype "passive"))
      (node (ref "R16") (pin "1") (pinfunction "1_1") (pintype "passive"))
    )
    (net (code "91") (name "XB2_MISO") (class "Default")
      (node (ref "IC5") (pin "11") (pinfunction "A1_11") (pintype "input"))
      (node (ref "J6") (pin "4") (pinfunction "4_4") (pintype "passive"))
    )
    (net (code "92") (name "XB2_MOSI") (class "Default")
      (node (ref "IC5") (pin "7") (pinfunction "Y2_7") (pintype "tri_state"))
      (node (ref "J7") (pin "1") (pinfunction "1_1") (pintype "passive"))
    )
    (net (code "93") (name "XB2_SCK") (class "Default")
      (node (ref "IC5") (pin "5") (pinfunction "Y3_5") (pintype "tri_state"))
      (node (ref "J7") (pin "8") (pinfunction "8_8") (pintype "passive"))
    )
    (net (code "94") (name "XB2_VCC") (class "Default")
      (node (ref "C17") (pin "2") (pinfunction "2_2") (pintype "passive"))
      (node (ref "C19") (pin "2") (pinfunction "2_2") (pintype "passive"))
      (node (ref "C21") (pin "2") (pinfunction "2_2") (pintype "passive"))
      (node (ref "IC3") (pin "3") (pinfunction "VCC_3") (pintype "power_in"))
      (node (ref "J6") (pin "1") (pinfunction "1_1") (pintype "passive"))
      (node (ref "R16") (pin "2") (pinfunction "2_2") (pintype "passive"))
      (node (ref "R21") (pin "1") (pinfunction "1_1") (pintype "passive"))
      (node (ref "R23") (pin "2") (pinfunction "2_2") (pintype "passive"))
      (node (ref "T1") (pin "5") (pinfunction "G_5") (pintype "passive"))
      (node (ref "T3") (pin "3") (pinfunction "D_3") (pintype "passive"))
    )
    (net (code "95") (name "unconnected-(IC6-CSB1-Pad16)") (class "Default")
      (node (ref "IC6") (pin "16") (pinfunction "CSB1_16") (pintype "bidirectional"))
    )
    (net (code "96") (name "unconnected-(IC6-CSB2-Pad5)") (class "Default")
      (node (ref "IC6") (pin "5") (pinfunction "CSB2_5") (pintype "bidirectional"))
    )
    (net (code "97") (name "unconnected-(IC6-CSB3-Pad20)") (class "Default")
      (node (ref "IC6") (pin "20") (pinfunction "CSB3_20") (pintype "bidirectional"))
    )
    (net (code "98") (name "unconnected-(IC6-DRDYM-Pad2)") (class "Default")
      (node (ref "IC6") (pin "2") (pinfunction "DRDYM_2") (pintype "bidirectional"))
    )
    (net (code "99") (name "unconnected-(IC6-INT1-Pad19)") (class "Default")
      (node (ref "IC6") (pin "19") (pinfunction "INT1_19") (pintype "output"))
    )
    (net (code "100") (name "unconnected-(IC6-INT2-Pad1)") (class "Default")
      (node (ref "IC6") (pin "1") (pinfunction "INT2_1") (pintype "output"))
    )
    (net (code "101") (name "unconnected-(IC6-INT3-Pad14)") (class "Default")
      (node (ref "IC6") (pin "14") (pinfunction "INT3_14") (pintype "output"))
    )
    (net (code "102") (name "unconnected-(IC6-INT4-Pad15)") (class "Default")
      (node (ref "IC6") (pin "15") (pinfunction "INT4_15") (pintype "output"))
    )
    (net (code "103") (name "unconnected-(IC6-INT5-Pad10)") (class "Default")
      (node (ref "IC6") (pin "10") (pinfunction "INT5_10") (pintype "bidirectional"))
    )
    (net (code "104") (name "unconnected-(J4-Pad6)") (class "Default")
      (node (ref "J4") (pin "6") (pinfunction "6_6") (pintype "passive"))
    )
    (net (code "105") (name "unconnected-(J4-Pad7)") (class "Default")
      (node (ref "J4") (pin "7") (pinfunction "7_7") (pintype "passive"))
    )
    (net (code "106") (name "unconnected-(J4-Pad8)") (class "Default")
      (node (ref "J4") (pin "8") (pinfunction "8_8") (pintype "passive"))
    )
    (net (code "107") (name "unconnected-(J4-Pad9)") (class "Default")
      (node (ref "J4") (pin "9") (pinfunction "9_9") (pintype "passive"))
    )
    (net (code "108") (name "unconnected-(J5-Pad3)") (class "Default")
      (node (ref "J5") (pin "3") (pinfunction "3_3") (pintype "passive"))
    )
    (net (code "109") (name "unconnected-(J5-Pad4)") (class "Default")
      (node (ref "J5") (pin "4") (pinfunction "4_4") (pintype "passive"))
    )
    (net (code "110") (name "unconnected-(J5-Pad5)") (class "Default")
      (node (ref "J5") (pin "5") (pinfunction "5_5") (pintype "passive"))
    )
    (net (code "111") (name "unconnected-(J5-Pad6)") (class "Default")
      (node (ref "J5") (pin "6") (pinfunction "6_6") (pintype "passive"))
    )
    (net (code "112") (name "unconnected-(J5-Pad9)") (class "Default")
      (node (ref "J5") (pin "9") (pinfunction "9_9") (pintype "passive"))
    )
    (net (code "113") (name "unconnected-(J5-Pad10)") (class "Default")
      (node (ref "J5") (pin "10") (pinfunction "10_10") (pintype "passive"))
    )
    (net (code "114") (name "unconnected-(J6-Pad6)") (class "Default")
      (node (ref "J6") (pin "6") (pinfunction "6_6") (pintype "passive"))
    )
    (net (code "115") (name "unconnected-(J6-Pad7)") (class "Default")
      (node (ref "J6") (pin "7") (pinfunction "7_7") (pintype "passive"))
    )
    (net (code "116") (name "unconnected-(J6-Pad8)") (class "Default")
      (node (ref "J6") (pin "8") (pinfunction "8_8") (pintype "passive"))
    )
    (net (code "117") (name "unconnected-(J6-Pad9)") (class "Default")
      (node (ref "J6") (pin "9") (pinfunction "9_9") (pintype "passive"))
    )
    (net (code "118") (name "unconnected-(J7-Pad3)") (class "Default")
      (node (ref "J7") (pin "3") (pinfunction "3_3") (pintype "passive"))
    )
    (net (code "119") (name "unconnected-(J7-Pad4)") (class "Default")
      (node (ref "J7") (pin "4") (pinfunction "4_4") (pintype "passive"))
    )
    (net (code "120") (name "unconnected-(J7-Pad5)") (class "Default")
      (node (ref "J7") (pin "5") (pinfunction "5_5") (pintype "passive"))
    )
    (net (code "121") (name "unconnected-(J7-Pad6)") (class "Default")
      (node (ref "J7") (pin "6") (pinfunction "6_6") (pintype "passive"))
    )
    (net (code "122") (name "unconnected-(J7-Pad9)") (class "Default")
      (node (ref "J7") (pin "9") (pinfunction "9_9") (pintype "passive"))
    )
    (net (code "123") (name "unconnected-(J7-Pad10)") (class "Default")
      (node (ref "J7") (pin "10") (pinfunction "10_10") (pintype "passive"))
    )
  )
)
